# SOC_level_indicator.net
KiCad netlist of a schematic drawn in EAGLE
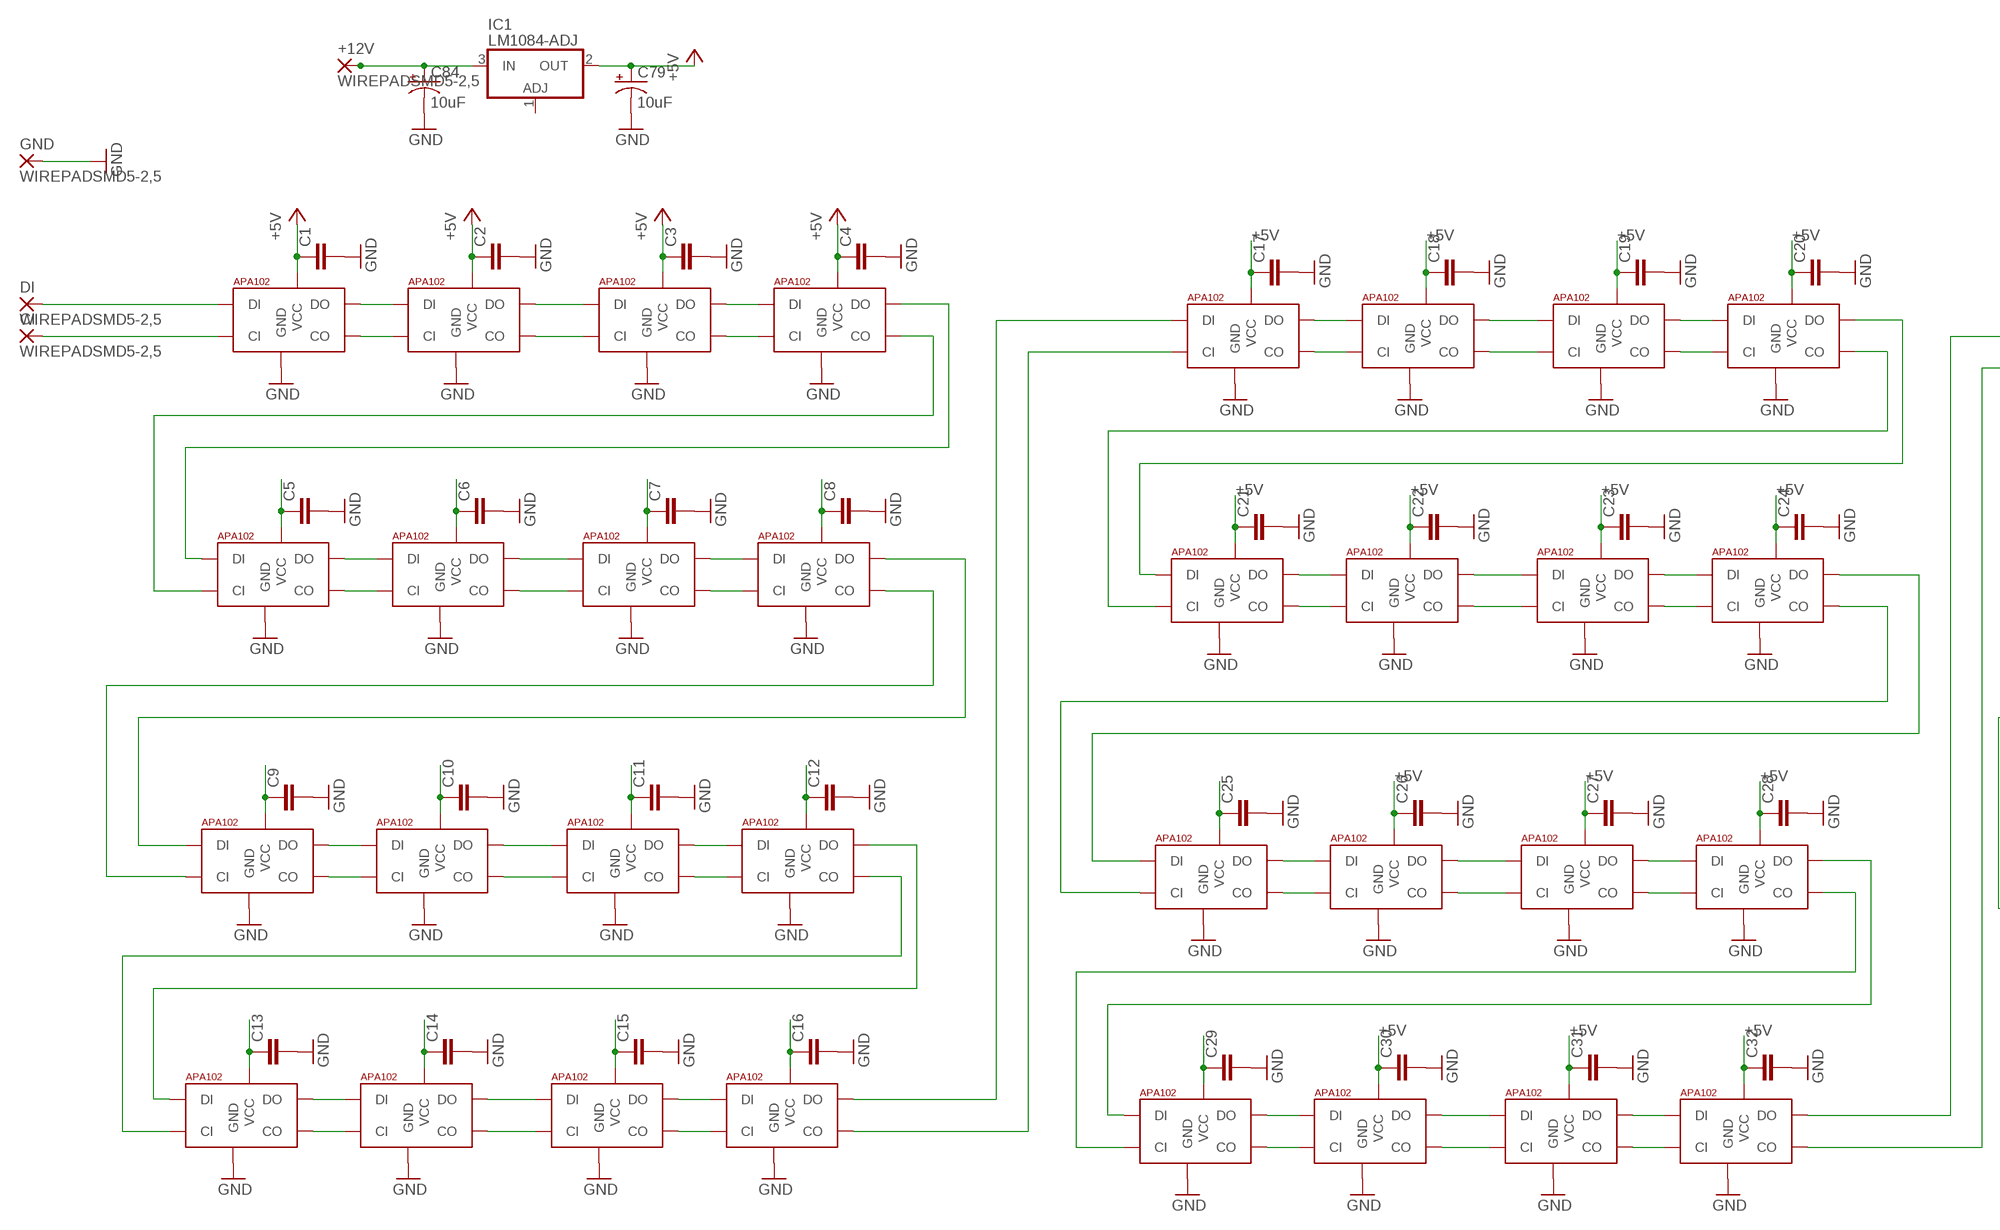
[diagram p0: schematic, sheet 1, part 1 of 2]
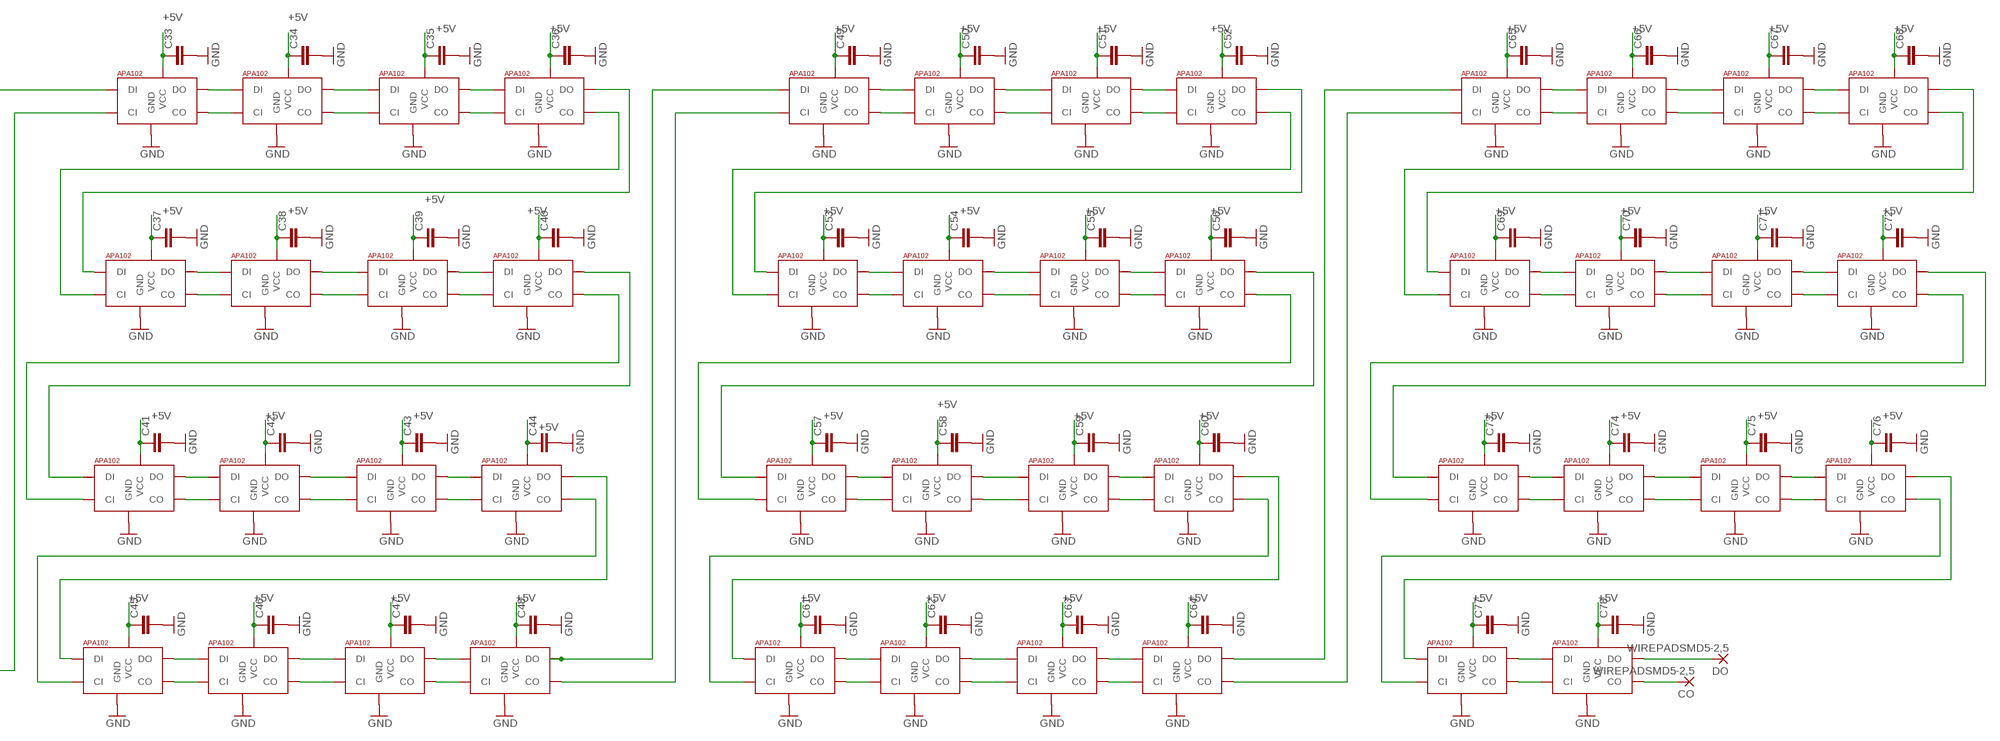
[diagram p1: schematic, sheet 1, part 2 of 2]

(export (version "E")
  (design (tool "Eeschema 10.0.6"))
  (components
    (comp (ref "+12V")
      (value "WIREPADSMD5-2,5")
      (footprint "eagle-import:5-2,5")
      (libsource (lib "eagle-import") (part "WIREPADSMD5-2,5"))
    )
    (comp (ref "C1")
      (value "CAP0603-CAP")
      (footprint "eagle-import:0603-CAP")
      (libsource (lib "eagle-import") (part "CAP0603-CAP"))
    )
    (comp (ref "C2")
      (value "CAP0603-CAP")
      (footprint "eagle-import:0603-CAP")
      (libsource (lib "eagle-import") (part "CAP0603-CAP"))
    )
    (comp (ref "C3")
      (value "CAP0603-CAP")
      (footprint "eagle-import:0603-CAP")
      (libsource (lib "eagle-import") (part "CAP0603-CAP"))
    )
    (comp (ref "C4")
      (value "CAP0603-CAP")
      (footprint "eagle-import:0603-CAP")
      (libsource (lib "eagle-import") (part "CAP0603-CAP"))
    )
    (comp (ref "C5")
      (value "CAP0603-CAP")
      (footprint "eagle-import:0603-CAP")
      (libsource (lib "eagle-import") (part "CAP0603-CAP"))
    )
    (comp (ref "C6")
      (value "CAP0603-CAP")
      (footprint "eagle-import:0603-CAP")
      (libsource (lib "eagle-import") (part "CAP0603-CAP"))
    )
    (comp (ref "C7")
      (value "CAP0603-CAP")
      (footprint "eagle-import:0603-CAP")
      (libsource (lib "eagle-import") (part "CAP0603-CAP"))
    )
    (comp (ref "C8")
      (value "CAP0603-CAP")
      (footprint "eagle-import:0603-CAP")
      (libsource (lib "eagle-import") (part "CAP0603-CAP"))
    )
    (comp (ref "C9")
      (value "CAP0603-CAP")
      (footprint "eagle-import:0603-CAP")
      (libsource (lib "eagle-import") (part "CAP0603-CAP"))
    )
    (comp (ref "C10")
      (value "CAP0603-CAP")
      (footprint "eagle-import:0603-CAP")
      (libsource (lib "eagle-import") (part "CAP0603-CAP"))
    )
    (comp (ref "C11")
      (value "CAP0603-CAP")
      (footprint "eagle-import:0603-CAP")
      (libsource (lib "eagle-import") (part "CAP0603-CAP"))
    )
    (comp (ref "C12")
      (value "CAP0603-CAP")
      (footprint "eagle-import:0603-CAP")
      (libsource (lib "eagle-import") (part "CAP0603-CAP"))
    )
    (comp (ref "C13")
      (value "CAP0603-CAP")
      (footprint "eagle-import:0603-CAP")
      (libsource (lib "eagle-import") (part "CAP0603-CAP"))
    )
    (comp (ref "C14")
      (value "CAP0603-CAP")
      (footprint "eagle-import:0603-CAP")
      (libsource (lib "eagle-import") (part "CAP0603-CAP"))
    )
    (comp (ref "C15")
      (value "CAP0603-CAP")
      (footprint "eagle-import:0603-CAP")
      (libsource (lib "eagle-import") (part "CAP0603-CAP"))
    )
    (comp (ref "C16")
      (value "CAP0603-CAP")
      (footprint "eagle-import:0603-CAP")
      (libsource (lib "eagle-import") (part "CAP0603-CAP"))
    )
    (comp (ref "C17")
      (value "CAP0603-CAP")
      (footprint "eagle-import:0603-CAP")
      (libsource (lib "eagle-import") (part "CAP0603-CAP"))
    )
    (comp (ref "C18")
      (value "CAP0603-CAP")
      (footprint "eagle-import:0603-CAP")
      (libsource (lib "eagle-import") (part "CAP0603-CAP"))
    )
    (comp (ref "C19")
      (value "CAP0603-CAP")
      (footprint "eagle-import:0603-CAP")
      (libsource (lib "eagle-import") (part "CAP0603-CAP"))
    )
    (comp (ref "C20")
      (value "CAP0603-CAP")
      (footprint "eagle-import:0603-CAP")
      (libsource (lib "eagle-import") (part "CAP0603-CAP"))
    )
    (comp (ref "C21")
      (value "CAP0603-CAP")
      (footprint "eagle-import:0603-CAP")
      (libsource (lib "eagle-import") (part "CAP0603-CAP"))
    )
    (comp (ref "C22")
      (value "CAP0603-CAP")
      (footprint "eagle-import:0603-CAP")
      (libsource (lib "eagle-import") (part "CAP0603-CAP"))
    )
    (comp (ref "C23")
      (value "CAP0603-CAP")
      (footprint "eagle-import:0603-CAP")
      (libsource (lib "eagle-import") (part "CAP0603-CAP"))
    )
    (comp (ref "C24")
      (value "CAP0603-CAP")
      (footprint "eagle-import:0603-CAP")
      (libsource (lib "eagle-import") (part "CAP0603-CAP"))
    )
    (comp (ref "C25")
      (value "CAP0603-CAP")
      (footprint "eagle-import:0603-CAP")
      (libsource (lib "eagle-import") (part "CAP0603-CAP"))
    )
    (comp (ref "C26")
      (value "CAP0603-CAP")
      (footprint "eagle-import:0603-CAP")
      (libsource (lib "eagle-import") (part "CAP0603-CAP"))
    )
    (comp (ref "C27")
      (value "CAP0603-CAP")
      (footprint "eagle-import:0603-CAP")
      (libsource (lib "eagle-import") (part "CAP0603-CAP"))
    )
    (comp (ref "C28")
      (value "CAP0603-CAP")
      (footprint "eagle-import:0603-CAP")
      (libsource (lib "eagle-import") (part "CAP0603-CAP"))
    )
    (comp (ref "C29")
      (value "CAP0603-CAP")
      (footprint "eagle-import:0603-CAP")
      (libsource (lib "eagle-import") (part "CAP0603-CAP"))
    )
    (comp (ref "C30")
      (value "CAP0603-CAP")
      (footprint "eagle-import:0603-CAP")
      (libsource (lib "eagle-import") (part "CAP0603-CAP"))
    )
    (comp (ref "C31")
      (value "CAP0603-CAP")
      (footprint "eagle-import:0603-CAP")
      (libsource (lib "eagle-import") (part "CAP0603-CAP"))
    )
    (comp (ref "C32")
      (value "CAP0603-CAP")
      (footprint "eagle-import:0603-CAP")
      (libsource (lib "eagle-import") (part "CAP0603-CAP"))
    )
    (comp (ref "C33")
      (value "CAP0603-CAP")
      (footprint "eagle-import:0603-CAP")
      (libsource (lib "eagle-import") (part "CAP0603-CAP"))
    )
    (comp (ref "C34")
      (value "CAP0603-CAP")
      (footprint "eagle-import:0603-CAP")
      (libsource (lib "eagle-import") (part "CAP0603-CAP"))
    )
    (comp (ref "C35")
      (value "CAP0603-CAP")
      (footprint "eagle-import:0603-CAP")
      (libsource (lib "eagle-import") (part "CAP0603-CAP"))
    )
    (comp (ref "C36")
      (value "CAP0603-CAP")
      (footprint "eagle-import:0603-CAP")
      (libsource (lib "eagle-import") (part "CAP0603-CAP"))
    )
    (comp (ref "C37")
      (value "CAP0603-CAP")
      (footprint "eagle-import:0603-CAP")
      (libsource (lib "eagle-import") (part "CAP0603-CAP"))
    )
    (comp (ref "C38")
      (value "CAP0603-CAP")
      (footprint "eagle-import:0603-CAP")
      (libsource (lib "eagle-import") (part "CAP0603-CAP"))
    )
    (comp (ref "C39")
      (value "CAP0603-CAP")
      (footprint "eagle-import:0603-CAP")
      (libsource (lib "eagle-import") (part "CAP0603-CAP"))
    )
    (comp (ref "C40")
      (value "CAP0603-CAP")
      (footprint "eagle-import:0603-CAP")
      (libsource (lib "eagle-import") (part "CAP0603-CAP"))
    )
    (comp (ref "C41")
      (value "CAP0603-CAP")
      (footprint "eagle-import:0603-CAP")
      (libsource (lib "eagle-import") (part "CAP0603-CAP"))
    )
    (comp (ref "C42")
      (value "CAP0603-CAP")
      (footprint "eagle-import:0603-CAP")
      (libsource (lib "eagle-import") (part "CAP0603-CAP"))
    )
    (comp (ref "C43")
      (value "CAP0603-CAP")
      (footprint "eagle-import:0603-CAP")
      (libsource (lib "eagle-import") (part "CAP0603-CAP"))
    )
    (comp (ref "C44")
      (value "CAP0603-CAP")
      (footprint "eagle-import:0603-CAP")
      (libsource (lib "eagle-import") (part "CAP0603-CAP"))
    )
    (comp (ref "C45")
      (value "CAP0603-CAP")
      (footprint "eagle-import:0603-CAP")
      (libsource (lib "eagle-import") (part "CAP0603-CAP"))
    )
    (comp (ref "C46")
      (value "CAP0603-CAP")
      (footprint "eagle-import:0603-CAP")
      (libsource (lib "eagle-import") (part "CAP0603-CAP"))
    )
    (comp (ref "C47")
      (value "CAP0603-CAP")
      (footprint "eagle-import:0603-CAP")
      (libsource (lib "eagle-import") (part "CAP0603-CAP"))
    )
    (comp (ref "C48")
      (value "CAP0603-CAP")
      (footprint "eagle-import:0603-CAP")
      (libsource (lib "eagle-import") (part "CAP0603-CAP"))
    )
    (comp (ref "C49")
      (value "CAP0603-CAP")
      (footprint "eagle-import:0603-CAP")
      (libsource (lib "eagle-import") (part "CAP0603-CAP"))
    )
    (comp (ref "C50")
      (value "CAP0603-CAP")
      (footprint "eagle-import:0603-CAP")
      (libsource (lib "eagle-import") (part "CAP0603-CAP"))
    )
    (comp (ref "C51")
      (value "CAP0603-CAP")
      (footprint "eagle-import:0603-CAP")
      (libsource (lib "eagle-import") (part "CAP0603-CAP"))
    )
    (comp (ref "C52")
      (value "CAP0603-CAP")
      (footprint "eagle-import:0603-CAP")
      (libsource (lib "eagle-import") (part "CAP0603-CAP"))
    )
    (comp (ref "C53")
      (value "CAP0603-CAP")
      (footprint "eagle-import:0603-CAP")
      (libsource (lib "eagle-import") (part "CAP0603-CAP"))
    )
    (comp (ref "C54")
      (value "CAP0603-CAP")
      (footprint "eagle-import:0603-CAP")
      (libsource (lib "eagle-import") (part "CAP0603-CAP"))
    )
    (comp (ref "C55")
      (value "CAP0603-CAP")
      (footprint "eagle-import:0603-CAP")
      (libsource (lib "eagle-import") (part "CAP0603-CAP"))
    )
    (comp (ref "C56")
      (value "CAP0603-CAP")
      (footprint "eagle-import:0603-CAP")
      (libsource (lib "eagle-import") (part "CAP0603-CAP"))
    )
    (comp (ref "C57")
      (value "CAP0603-CAP")
      (footprint "eagle-import:0603-CAP")
      (libsource (lib "eagle-import") (part "CAP0603-CAP"))
    )
    (comp (ref "C58")
      (value "CAP0603-CAP")
      (footprint "eagle-import:0603-CAP")
      (libsource (lib "eagle-import") (part "CAP0603-CAP"))
    )
    (comp (ref "C59")
      (value "CAP0603-CAP")
      (footprint "eagle-import:0603-CAP")
      (libsource (lib "eagle-import") (part "CAP0603-CAP"))
    )
    (comp (ref "C60")
      (value "CAP0603-CAP")
      (footprint "eagle-import:0603-CAP")
      (libsource (lib "eagle-import") (part "CAP0603-CAP"))
    )
    (comp (ref "C61")
      (value "CAP0603-CAP")
      (footprint "eagle-import:0603-CAP")
      (libsource (lib "eagle-import") (part "CAP0603-CAP"))
    )
    (comp (ref "C62")
      (value "CAP0603-CAP")
      (footprint "eagle-import:0603-CAP")
      (libsource (lib "eagle-import") (part "CAP0603-CAP"))
    )
    (comp (ref "C63")
      (value "CAP0603-CAP")
      (footprint "eagle-import:0603-CAP")
      (libsource (lib "eagle-import") (part "CAP0603-CAP"))
    )
    (comp (ref "C64")
      (value "CAP0603-CAP")
      (footprint "eagle-import:0603-CAP")
      (libsource (lib "eagle-import") (part "CAP0603-CAP"))
    )
    (comp (ref "C65")
      (value "CAP0603-CAP")
      (footprint "eagle-import:0603-CAP")
      (libsource (lib "eagle-import") (part "CAP0603-CAP"))
    )
    (comp (ref "C66")
      (value "CAP0603-CAP")
      (footprint "eagle-import:0603-CAP")
      (libsource (lib "eagle-import") (part "CAP0603-CAP"))
    )
    (comp (ref "C67")
      (value "CAP0603-CAP")
      (footprint "eagle-import:0603-CAP")
      (libsource (lib "eagle-import") (part "CAP0603-CAP"))
    )
    (comp (ref "C68")
      (value "CAP0603-CAP")
      (footprint "eagle-import:0603-CAP")
      (libsource (lib "eagle-import") (part "CAP0603-CAP"))
    )
    (comp (ref "C69")
      (value "CAP0603-CAP")
      (footprint "eagle-import:0603-CAP")
      (libsource (lib "eagle-import") (part "CAP0603-CAP"))
    )
    (comp (ref "C70")
      (value "CAP0603-CAP")
      (footprint "eagle-import:0603-CAP")
      (libsource (lib "eagle-import") (part "CAP0603-CAP"))
    )
    (comp (ref "C71")
      (value "CAP0603-CAP")
      (footprint "eagle-import:0603-CAP")
      (libsource (lib "eagle-import") (part "CAP0603-CAP"))
    )
    (comp (ref "C72")
      (value "CAP0603-CAP")
      (footprint "eagle-import:0603-CAP")
      (libsource (lib "eagle-import") (part "CAP0603-CAP"))
    )
    (comp (ref "C73")
      (value "CAP0603-CAP")
      (footprint "eagle-import:0603-CAP")
      (libsource (lib "eagle-import") (part "CAP0603-CAP"))
    )
    (comp (ref "C74")
      (value "CAP0603-CAP")
      (footprint "eagle-import:0603-CAP")
      (libsource (lib "eagle-import") (part "CAP0603-CAP"))
    )
    (comp (ref "C75")
      (value "CAP0603-CAP")
      (footprint "eagle-import:0603-CAP")
      (libsource (lib "eagle-import") (part "CAP0603-CAP"))
    )
    (comp (ref "C76")
      (value "CAP0603-CAP")
      (footprint "eagle-import:0603-CAP")
      (libsource (lib "eagle-import") (part "CAP0603-CAP"))
    )
    (comp (ref "C77")
      (value "CAP0603-CAP")
      (footprint "eagle-import:0603-CAP")
      (libsource (lib "eagle-import") (part "CAP0603-CAP"))
    )
    (comp (ref "C78")
      (value "CAP0603-CAP")
      (footprint "eagle-import:0603-CAP")
      (libsource (lib "eagle-import") (part "CAP0603-CAP"))
    )
    (comp (ref "C79")
      (value "10uF")
      (footprint "eagle-import:EIA3216")
      (libsource (lib "eagle-import") (part "10UF-16V-10%(TANT)"))
    )
    (comp (ref "C84")
      (value "10uF")
      (footprint "eagle-import:EIA3216")
      (libsource (lib "eagle-import") (part "10UF-16V-10%(TANT)"))
    )
    (comp (ref "CI")
      (value "WIREPADSMD5-2,5")
      (footprint "eagle-import:5-2,5")
      (libsource (lib "eagle-import") (part "WIREPADSMD5-2,5"))
    )
    (comp (ref "CO")
      (value "WIREPADSMD5-2,5")
      (footprint "eagle-import:5-2,5")
      (libsource (lib "eagle-import") (part "WIREPADSMD5-2,5"))
    )
    (comp (ref "DI")
      (value "WIREPADSMD5-2,5")
      (footprint "eagle-import:5-2,5")
      (libsource (lib "eagle-import") (part "WIREPADSMD5-2,5"))
    )
    (comp (ref "DO")
      (value "WIREPADSMD5-2,5")
      (footprint "eagle-import:5-2,5")
      (libsource (lib "eagle-import") (part "WIREPADSMD5-2,5"))
    )
    (comp (ref "GND")
      (value "WIREPADSMD5-2,5")
      (footprint "eagle-import:5-2,5")
      (libsource (lib "eagle-import") (part "WIREPADSMD5-2,5"))
    )
    (comp (ref "IC1")
      (value "LM1084-ADJ")
      (footprint "eagle-import:TO263-3")
      (libsource (lib "eagle-import") (part "LM1084-ADJ"))
    )
    (comp (ref "U$1")
      (value "APA1025050")
      (footprint "eagle-import:APA102_5050")
      (libsource (lib "eagle-import") (part "APA1025050"))
    )
    (comp (ref "U$2")
      (value "APA1025050")
      (footprint "eagle-import:APA102_5050")
      (libsource (lib "eagle-import") (part "APA1025050"))
    )
    (comp (ref "U$3")
      (value "APA1025050")
      (footprint "eagle-import:APA102_5050")
      (libsource (lib "eagle-import") (part "APA1025050"))
    )
    (comp (ref "U$4")
      (value "APA1025050")
      (footprint "eagle-import:APA102_5050")
      (libsource (lib "eagle-import") (part "APA1025050"))
    )
    (comp (ref "U$5")
      (value "APA1025050")
      (footprint "eagle-import:APA102_5050")
      (libsource (lib "eagle-import") (part "APA1025050"))
    )
    (comp (ref "U$6")
      (value "APA1025050")
      (footprint "eagle-import:APA102_5050")
      (libsource (lib "eagle-import") (part "APA1025050"))
    )
    (comp (ref "U$7")
      (value "APA1025050")
      (footprint "eagle-import:APA102_5050")
      (libsource (lib "eagle-import") (part "APA1025050"))
    )
    (comp (ref "U$8")
      (value "APA1025050")
      (footprint "eagle-import:APA102_5050")
      (libsource (lib "eagle-import") (part "APA1025050"))
    )
    (comp (ref "U$9")
      (value "APA1025050")
      (footprint "eagle-import:APA102_5050")
      (libsource (lib "eagle-import") (part "APA1025050"))
    )
    (comp (ref "U$10")
      (value "APA1025050")
      (footprint "eagle-import:APA102_5050")
      (libsource (lib "eagle-import") (part "APA1025050"))
    )
    (comp (ref "U$11")
      (value "APA1025050")
      (footprint "eagle-import:APA102_5050")
      (libsource (lib "eagle-import") (part "APA1025050"))
    )
    (comp (ref "U$12")
      (value "APA1025050")
      (footprint "eagle-import:APA102_5050")
      (libsource (lib "eagle-import") (part "APA1025050"))
    )
    (comp (ref "U$13")
      (value "APA1025050")
      (footprint "eagle-import:APA102_5050")
      (libsource (lib "eagle-import") (part "APA1025050"))
    )
    (comp (ref "U$14")
      (value "APA1025050")
      (footprint "eagle-import:APA102_5050")
      (libsource (lib "eagle-import") (part "APA1025050"))
    )
    (comp (ref "U$15")
      (value "APA1025050")
      (footprint "eagle-import:APA102_5050")
      (libsource (lib "eagle-import") (part "APA1025050"))
    )
    (comp (ref "U$16")
      (value "APA1025050")
      (footprint "eagle-import:APA102_5050")
      (libsource (lib "eagle-import") (part "APA1025050"))
    )
    (comp (ref "U$17")
      (value "APA1025050")
      (footprint "eagle-import:APA102_5050")
      (libsource (lib "eagle-import") (part "APA1025050"))
    )
    (comp (ref "U$18")
      (value "APA1025050")
      (footprint "eagle-import:APA102_5050")
      (libsource (lib "eagle-import") (part "APA1025050"))
    )
    (comp (ref "U$19")
      (value "APA1025050")
      (footprint "eagle-import:APA102_5050")
      (libsource (lib "eagle-import") (part "APA1025050"))
    )
    (comp (ref "U$20")
      (value "APA1025050")
      (footprint "eagle-import:APA102_5050")
      (libsource (lib "eagle-import") (part "APA1025050"))
    )
    (comp (ref "U$21")
      (value "APA1025050")
      (footprint "eagle-import:APA102_5050")
      (libsource (lib "eagle-import") (part "APA1025050"))
    )
    (comp (ref "U$22")
      (value "APA1025050")
      (footprint "eagle-import:APA102_5050")
      (libsource (lib "eagle-import") (part "APA1025050"))
    )
    (comp (ref "U$23")
      (value "APA1025050")
      (footprint "eagle-import:APA102_5050")
      (libsource (lib "eagle-import") (part "APA1025050"))
    )
    (comp (ref "U$24")
      (value "APA1025050")
      (footprint "eagle-import:APA102_5050")
      (libsource (lib "eagle-import") (part "APA1025050"))
    )
    (comp (ref "U$25")
      (value "APA1025050")
      (footprint "eagle-import:APA102_5050")
      (libsource (lib "eagle-import") (part "APA1025050"))
    )
    (comp (ref "U$26")
      (value "APA1025050")
      (footprint "eagle-import:APA102_5050")
      (libsource (lib "eagle-import") (part "APA1025050"))
    )
    (comp (ref "U$27")
      (value "APA1025050")
      (footprint "eagle-import:APA102_5050")
      (libsource (lib "eagle-import") (part "APA1025050"))
    )
    (comp (ref "U$28")
      (value "APA1025050")
      (footprint "eagle-import:APA102_5050")
      (libsource (lib "eagle-import") (part "APA1025050"))
    )
    (comp (ref "U$29")
      (value "APA1025050")
      (footprint "eagle-import:APA102_5050")
      (libsource (lib "eagle-import") (part "APA1025050"))
    )
    (comp (ref "U$30")
      (value "APA1025050")
      (footprint "eagle-import:APA102_5050")
      (libsource (lib "eagle-import") (part "APA1025050"))
    )
    (comp (ref "U$31")
      (value "APA1025050")
      (footprint "eagle-import:APA102_5050")
      (libsource (lib "eagle-import") (part "APA1025050"))
    )
    (comp (ref "U$32")
      (value "APA1025050")
      (footprint "eagle-import:APA102_5050")
      (libsource (lib "eagle-import") (part "APA1025050"))
    )
    (comp (ref "U$33")
      (value "APA1025050")
      (footprint "eagle-import:APA102_5050")
      (libsource (lib "eagle-import") (part "APA1025050"))
    )
    (comp (ref "U$34")
      (value "APA1025050")
      (footprint "eagle-import:APA102_5050")
      (libsource (lib "eagle-import") (part "APA1025050"))
    )
    (comp (ref "U$35")
      (value "APA1025050")
      (footprint "eagle-import:APA102_5050")
      (libsource (lib "eagle-import") (part "APA1025050"))
    )
    (comp (ref "U$36")
      (value "APA1025050")
      (footprint "eagle-import:APA102_5050")
      (libsource (lib "eagle-import") (part "APA1025050"))
    )
    (comp (ref "U$37")
      (value "APA1025050")
      (footprint "eagle-import:APA102_5050")
      (libsource (lib "eagle-import") (part "APA1025050"))
    )
    (comp (ref "U$38")
      (value "APA1025050")
      (footprint "eagle-import:APA102_5050")
      (libsource (lib "eagle-import") (part "APA1025050"))
    )
    (comp (ref "U$39")
      (value "APA1025050")
      (footprint "eagle-import:APA102_5050")
      (libsource (lib "eagle-import") (part "APA1025050"))
    )
    (comp (ref "U$40")
      (value "APA1025050")
      (footprint "eagle-import:APA102_5050")
      (libsource (lib "eagle-import") (part "APA1025050"))
    )
    (comp (ref "U$41")
      (value "APA1025050")
      (footprint "eagle-import:APA102_5050")
      (libsource (lib "eagle-import") (part "APA1025050"))
    )
    (comp (ref "U$42")
      (value "APA1025050")
      (footprint "eagle-import:APA102_5050")
      (libsource (lib "eagle-import") (part "APA1025050"))
    )
    (comp (ref "U$43")
      (value "APA1025050")
      (footprint "eagle-import:APA102_5050")
      (libsource (lib "eagle-import") (part "APA1025050"))
    )
    (comp (ref "U$44")
      (value "APA1025050")
      (footprint "eagle-import:APA102_5050")
      (libsource (lib "eagle-import") (part "APA1025050"))
    )
    (comp (ref "U$45")
      (value "APA1025050")
      (footprint "eagle-import:APA102_5050")
      (libsource (lib "eagle-import") (part "APA1025050"))
    )
    (comp (ref "U$46")
      (value "APA1025050")
      (footprint "eagle-import:APA102_5050")
      (libsource (lib "eagle-import") (part "APA1025050"))
    )
    (comp (ref "U$47")
      (value "APA1025050")
      (footprint "eagle-import:APA102_5050")
      (libsource (lib "eagle-import") (part "APA1025050"))
    )
    (comp (ref "U$48")
      (value "APA1025050")
      (footprint "eagle-import:APA102_5050")
      (libsource (lib "eagle-import") (part "APA1025050"))
    )
    (comp (ref "U$49")
      (value "APA1025050")
      (footprint "eagle-import:APA102_5050")
      (libsource (lib "eagle-import") (part "APA1025050"))
    )
    (comp (ref "U$50")
      (value "APA1025050")
      (footprint "eagle-import:APA102_5050")
      (libsource (lib "eagle-import") (part "APA1025050"))
    )
    (comp (ref "U$51")
      (value "APA1025050")
      (footprint "eagle-import:APA102_5050")
      (libsource (lib "eagle-import") (part "APA1025050"))
    )
    (comp (ref "U$52")
      (value "APA1025050")
      (footprint "eagle-import:APA102_5050")
      (libsource (lib "eagle-import") (part "APA1025050"))
    )
    (comp (ref "U$53")
      (value "APA1025050")
      (footprint "eagle-import:APA102_5050")
      (libsource (lib "eagle-import") (part "APA1025050"))
    )
    (comp (ref "U$54")
      (value "APA1025050")
      (footprint "eagle-import:APA102_5050")
      (libsource (lib "eagle-import") (part "APA1025050"))
    )
    (comp (ref "U$55")
      (value "APA1025050")
      (footprint "eagle-import:APA102_5050")
      (libsource (lib "eagle-import") (part "APA1025050"))
    )
    (comp (ref "U$56")
      (value "APA1025050")
      (footprint "eagle-import:APA102_5050")
      (libsource (lib "eagle-import") (part "APA1025050"))
    )
    (comp (ref "U$57")
      (value "APA1025050")
      (footprint "eagle-import:APA102_5050")
      (libsource (lib "eagle-import") (part "APA1025050"))
    )
    (comp (ref "U$58")
      (value "APA1025050")
      (footprint "eagle-import:APA102_5050")
      (libsource (lib "eagle-import") (part "APA1025050"))
    )
    (comp (ref "U$59")
      (value "APA1025050")
      (footprint "eagle-import:APA102_5050")
      (libsource (lib "eagle-import") (part "APA1025050"))
    )
    (comp (ref "U$60")
      (value "APA1025050")
      (footprint "eagle-import:APA102_5050")
      (libsource (lib "eagle-import") (part "APA1025050"))
    )
    (comp (ref "U$61")
      (value "APA1025050")
      (footprint "eagle-import:APA102_5050")
      (libsource (lib "eagle-import") (part "APA1025050"))
    )
    (comp (ref "U$62")
      (value "APA1025050")
      (footprint "eagle-import:APA102_5050")
      (libsource (lib "eagle-import") (part "APA1025050"))
    )
    (comp (ref "U$63")
      (value "APA1025050")
      (footprint "eagle-import:APA102_5050")
      (libsource (lib "eagle-import") (part "APA1025050"))
    )
    (comp (ref "U$64")
      (value "APA1025050")
      (footprint "eagle-import:APA102_5050")
      (libsource (lib "eagle-import") (part "APA1025050"))
    )
    (comp (ref "U$65")
      (value "APA1025050")
      (footprint "eagle-import:APA102_5050")
      (libsource (lib "eagle-import") (part "APA1025050"))
    )
    (comp (ref "U$66")
      (value "APA1025050")
      (footprint "eagle-import:APA102_5050")
      (libsource (lib "eagle-import") (part "APA1025050"))
    )
    (comp (ref "U$67")
      (value "APA1025050")
      (footprint "eagle-import:APA102_5050")
      (libsource (lib "eagle-import") (part "APA1025050"))
    )
    (comp (ref "U$68")
      (value "APA1025050")
      (footprint "eagle-import:APA102_5050")
      (libsource (lib "eagle-import") (part "APA1025050"))
    )
    (comp (ref "U$69")
      (value "APA1025050")
      (footprint "eagle-import:APA102_5050")
      (libsource (lib "eagle-import") (part "APA1025050"))
    )
    (comp (ref "U$70")
      (value "APA1025050")
      (footprint "eagle-import:APA102_5050")
      (libsource (lib "eagle-import") (part "APA1025050"))
    )
    (comp (ref "U$71")
      (value "APA1025050")
      (footprint "eagle-import:APA102_5050")
      (libsource (lib "eagle-import") (part "APA1025050"))
    )
    (comp (ref "U$72")
      (value "APA1025050")
      (footprint "eagle-import:APA102_5050")
      (libsource (lib "eagle-import") (part "APA1025050"))
    )
    (comp (ref "U$73")
      (value "APA1025050")
      (footprint "eagle-import:APA102_5050")
      (libsource (lib "eagle-import") (part "APA1025050"))
    )
    (comp (ref "U$74")
      (value "APA1025050")
      (footprint "eagle-import:APA102_5050")
      (libsource (lib "eagle-import") (part "APA1025050"))
    )
    (comp (ref "U$75")
      (value "APA1025050")
      (footprint "eagle-import:APA102_5050")
      (libsource (lib "eagle-import") (part "APA1025050"))
    )
    (comp (ref "U$76")
      (value "APA1025050")
      (footprint "eagle-import:APA102_5050")
      (libsource (lib "eagle-import") (part "APA1025050"))
    )
    (comp (ref "U$77")
      (value "APA1025050")
      (footprint "eagle-import:APA102_5050")
      (libsource (lib "eagle-import") (part "APA1025050"))
    )
    (comp (ref "U$78")
      (value "APA1025050")
      (footprint "eagle-import:APA102_5050")
      (libsource (lib "eagle-import") (part "APA1025050"))
    )
  )
  (nets
    (net (code "1") (name "+5V") (class "Default")
      (node (ref "C1") (pin "1") (pinfunction "1_1") (pintype "passive"))
      (node (ref "C10") (pin "1") (pinfunction "1_1") (pintype "passive"))
      (node (ref "C11") (pin "1") (pinfunction "1_1") (pintype "passive"))
      (node (ref "C12") (pin "1") (pinfunction "1_1") (pintype "passive"))
      (node (ref "C13") (pin "1") (pinfunction "1_1") (pintype "passive"))
      (node (ref "C14") (pin "1") (pinfunction "1_1") (pintype "passive"))
      (node (ref "C15") (pin "1") (pinfunction "1_1") (pintype "passive"))
      (node (ref "C16") (pin "1") (pinfunction "1_1") (pintype "passive"))
      (node (ref "C17") (pin "1") (pinfunction "1_1") (pintype "passive"))
      (node (ref "C18") (pin "1") (pinfunction "1_1") (pintype "passive"))
      (node (ref "C19") (pin "1") (pinfunction "1_1") (pintype "passive"))
      (node (ref "C2") (pin "1") (pinfunction "1_1") (pintype "passive"))
      (node (ref "C20") (pin "1") (pinfunction "1_1") (pintype "passive"))
      (node (ref "C21") (pin "1") (pinfunction "1_1") (pintype "passive"))
      (node (ref "C22") (pin "1") (pinfunction "1_1") (pintype "passive"))
      (node (ref "C23") (pin "1") (pinfunction "1_1") (pintype "passive"))
      (node (ref "C24") (pin "1") (pinfunction "1_1") (pintype "passive"))
      (node (ref "C25") (pin "1") (pinfunction "1_1") (pintype "passive"))
      (node (ref "C26") (pin "1") (pinfunction "1_1") (pintype "passive"))
      (node (ref "C27") (pin "1") (pinfunction "1_1") (pintype "passive"))
      (node (ref "C28") (pin "1") (pinfunction "1_1") (pintype "passive"))
      (node (ref "C29") (pin "1") (pinfunction "1_1") (pintype "passive"))
      (node (ref "C3") (pin "1") (pinfunction "1_1") (pintype "passive"))
      (node (ref "C30") (pin "1") (pinfunction "1_1") (pintype "passive"))
      (node (ref "C31") (pin "1") (pinfunction "1_1") (pintype "passive"))
      (node (ref "C32") (pin "1") (pinfunction "1_1") (pintype "passive"))
      (node (ref "C33") (pin "1") (pinfunction "1_1") (pintype "passive"))
      (node (ref "C34") (pin "1") (pinfunction "1_1") (pintype "passive"))
      (node (ref "C35") (pin "1") (pinfunction "1_1") (pintype "passive"))
      (node (ref "C36") (pin "1") (pinfunction "1_1") (pintype "passive"))
      (node (ref "C37") (pin "1") (pinfunction "1_1") (pintype "passive"))
      (node (ref "C38") (pin "1") (pinfunction "1_1") (pintype "passive"))
      (node (ref "C39") (pin "1") (pinfunction "1_1") (pintype "passive"))
      (node (ref "C4") (pin "1") (pinfunction "1_1") (pintype "passive"))
      (node (ref "C40") (pin "1") (pinfunction "1_1") (pintype "passive"))
      (node (ref "C41") (pin "1") (pinfunction "1_1") (pintype "passive"))
      (node (ref "C42") (pin "1") (pinfunction "1_1") (pintype "passive"))
      (node (ref "C43") (pin "1") (pinfunction "1_1") (pintype "passive"))
      (node (ref "C44") (pin "1") (pinfunction "1_1") (pintype "passive"))
      (node (ref "C45") (pin "1") (pinfunction "1_1") (pintype "passive"))
      (node (ref "C46") (pin "1") (pinfunction "1_1") (pintype "passive"))
      (node (ref "C47") (pin "1") (pinfunction "1_1") (pintype "passive"))
      (node (ref "C48") (pin "1") (pinfunction "1_1") (pintype "passive"))
      (node (ref "C49") (pin "1") (pinfunction "1_1") (pintype "passive"))
      (node (ref "C5") (pin "1") (pinfunction "1_1") (pintype "passive"))
      (node (ref "C50") (pin "1") (pinfunction "1_1") (pintype "passive"))
      (node (ref "C51") (pin "1") (pinfunction "1_1") (pintype "passive"))
      (node (ref "C52") (pin "1") (pinfunction "1_1") (pintype "passive"))
      (node (ref "C53") (pin "1") (pinfunction "1_1") (pintype "passive"))
      (node (ref "C54") (pin "1") (pinfunction "1_1") (pintype "passive"))
      (node (ref "C55") (pin "1") (pinfunction "1_1") (pintype "passive"))
      (node (ref "C56") (pin "1") (pinfunction "1_1") (pintype "passive"))
      (node (ref "C57") (pin "1") (pinfunction "1_1") (pintype "passive"))
      (node (ref "C58") (pin "1") (pinfunction "1_1") (pintype "passive"))
      (node (ref "C59") (pin "1") (pinfunction "1_1") (pintype "passive"))
      (node (ref "C6") (pin "1") (pinfunction "1_1") (pintype "passive"))
      (node (ref "C60") (pin "1") (pinfunction "1_1") (pintype "passive"))
      (node (ref "C61") (pin "1") (pinfunction "1_1") (pintype "passive"))
      (node (ref "C62") (pin "1") (pinfunction "1_1") (pintype "passive"))
      (node (ref "C63") (pin "1") (pinfunction "1_1") (pintype "passive"))
      (node (ref "C64") (pin "1") (pinfunction "1_1") (pintype "passive"))
      (node (ref "C65") (pin "1") (pinfunction "1_1") (pintype "passive"))
      (node (ref "C66") (pin "1") (pinfunction "1_1") (pintype "passive"))
      (node (ref "C67") (pin "1") (pinfunction "1_1") (pintype "passive"))
      (node (ref "C68") (pin "1") (pinfunction "1_1") (pintype "passive"))
      (node (ref "C69") (pin "1") (pinfunction "1_1") (pintype "passive"))
      (node (ref "C7") (pin "1") (pinfunction "1_1") (pintype "passive"))
      (node (ref "C70") (pin "1") (pinfunction "1_1") (pintype "passive"))
      (node (ref "C71") (pin "1") (pinfunction "1_1") (pintype "passive"))
      (node (ref "C72") (pin "1") (pinfunction "1_1") (pintype "passive"))
      (node (ref "C73") (pin "1") (pinfunction "1_1") (pintype "passive"))
      (node (ref "C74") (pin "1") (pinfunction "1_1") (pintype "passive"))
      (node (ref "C75") (pin "1") (pinfunction "1_1") (pintype "passive"))
      (node (ref "C76") (pin "1") (pinfunction "1_1") (pintype "passive"))
      (node (ref "C77") (pin "1") (pinfunction "1_1") (pintype "passive"))
      (node (ref "C78") (pin "1") (pinfunction "1_1") (pintype "passive"))
      (node (ref "C79") (pin "A") (pinfunction "+_A") (pintype "passive"))
      (node (ref "C8") (pin "1") (pinfunction "1_1") (pintype "passive"))
      (node (ref "C9") (pin "1") (pinfunction "1_1") (pintype "passive"))
      (node (ref "IC1") (pin "2") (pinfunction "OUT_2") (pintype "output"))
      (node (ref "U$1") (pin "1") (pinfunction "VCC_1") (pintype "bidirectional"))
      (node (ref "U$10") (pin "1") (pinfunction "VCC_1") (pintype "bidirectional"))
      (node (ref "U$11") (pin "1") (pinfunction "VCC_1") (pintype "bidirectional"))
      (node (ref "U$12") (pin "1") (pinfunction "VCC_1") (pintype "bidirectional"))
      (node (ref "U$13") (pin "1") (pinfunction "VCC_1") (pintype "bidirectional"))
      (node (ref "U$14") (pin "1") (pinfunction "VCC_1") (pintype "bidirectional"))
      (node (ref "U$15") (pin "1") (pinfunction "VCC_1") (pintype "bidirectional"))
      (node (ref "U$16") (pin "1") (pinfunction "VCC_1") (pintype "bidirectional"))
      (node (ref "U$17") (pin "1") (pinfunction "VCC_1") (pintype "bidirectional"))
      (node (ref "U$18") (pin "1") (pinfunction "VCC_1") (pintype "bidirectional"))
      (node (ref "U$19") (pin "1") (pinfunction "VCC_1") (pintype "bidirectional"))
      (node (ref "U$2") (pin "1") (pinfunction "VCC_1") (pintype "bidirectional"))
      (node (ref "U$20") (pin "1") (pinfunction "VCC_1") (pintype "bidirectional"))
      (node (ref "U$21") (pin "1") (pinfunction "VCC_1") (pintype "bidirectional"))
      (node (ref "U$22") (pin "1") (pinfunction "VCC_1") (pintype "bidirectional"))
      (node (ref "U$23") (pin "1") (pinfunction "VCC_1") (pintype "bidirectional"))
      (node (ref "U$24") (pin "1") (pinfunction "VCC_1") (pintype "bidirectional"))
      (node (ref "U$25") (pin "1") (pinfunction "VCC_1") (pintype "bidirectional"))
      (node (ref "U$26") (pin "1") (pinfunction "VCC_1") (pintype "bidirectional"))
      (node (ref "U$27") (pin "1") (pinfunction "VCC_1") (pintype "bidirectional"))
      (node (ref "U$28") (pin "1") (pinfunction "VCC_1") (pintype "bidirectional"))
      (node (ref "U$29") (pin "1") (pinfunction "VCC_1") (pintype "bidirectional"))
      (node (ref "U$3") (pin "1") (pinfunction "VCC_1") (pintype "bidirectional"))
      (node (ref "U$30") (pin "1") (pinfunction "VCC_1") (pintype "bidirectional"))
      (node (ref "U$31") (pin "1") (pinfunction "VCC_1") (pintype "bidirectional"))
      (node (ref "U$32") (pin "1") (pinfunction "VCC_1") (pintype "bidirectional"))
      (node (ref "U$33") (pin "1") (pinfunction "VCC_1") (pintype "bidirectional"))
      (node (ref "U$34") (pin "1") (pinfunction "VCC_1") (pintype "bidirectional"))
      (node (ref "U$35") (pin "1") (pinfunction "VCC_1") (pintype "bidirectional"))
      (node (ref "U$36") (pin "1") (pinfunction "VCC_1") (pintype "bidirectional"))
      (node (ref "U$37") (pin "1") (pinfunction "VCC_1") (pintype "bidirectional"))
      (node (ref "U$38") (pin "1") (pinfunction "VCC_1") (pintype "bidirectional"))
      (node (ref "U$39") (pin "1") (pinfunction "VCC_1") (pintype "bidirectional"))
      (node (ref "U$4") (pin "1") (pinfunction "VCC_1") (pintype "bidirectional"))
      (node (ref "U$40") (pin "1") (pinfunction "VCC_1") (pintype "bidirectional"))
      (node (ref "U$41") (pin "1") (pinfunction "VCC_1") (pintype "bidirectional"))
      (node (ref "U$42") (pin "1") (pinfunction "VCC_1") (pintype "bidirectional"))
      (node (ref "U$43") (pin "1") (pinfunction "VCC_1") (pintype "bidirectional"))
      (node (ref "U$44") (pin "1") (pinfunction "VCC_1") (pintype "bidirectional"))
      (node (ref "U$45") (pin "1") (pinfunction "VCC_1") (pintype "bidirectional"))
      (node (ref "U$46") (pin "1") (pinfunction "VCC_1") (pintype "bidirectional"))
      (node (ref "U$47") (pin "1") (pinfunction "VCC_1") (pintype "bidirectional"))
      (node (ref "U$48") (pin "1") (pinfunction "VCC_1") (pintype "bidirectional"))
      (node (ref "U$49") (pin "1") (pinfunction "VCC_1") (pintype "bidirectional"))
      (node (ref "U$5") (pin "1") (pinfunction "VCC_1") (pintype "bidirectional"))
      (node (ref "U$50") (pin "1") (pinfunction "VCC_1") (pintype "bidirectional"))
      (node (ref "U$51") (pin "1") (pinfunction "VCC_1") (pintype "bidirectional"))
      (node (ref "U$52") (pin "1") (pinfunction "VCC_1") (pintype "bidirectional"))
      (node (ref "U$53") (pin "1") (pinfunction "VCC_1") (pintype "bidirectional"))
      (node (ref "U$54") (pin "1") (pinfunction "VCC_1") (pintype "bidirectional"))
      (node (ref "U$55") (pin "1") (pinfunction "VCC_1") (pintype "bidirectional"))
      (node (ref "U$56") (pin "1") (pinfunction "VCC_1") (pintype "bidirectional"))
      (node (ref "U$57") (pin "1") (pinfunction "VCC_1") (pintype "bidirectional"))
      (node (ref "U$58") (pin "1") (pinfunction "VCC_1") (pintype "bidirectional"))
      (node (ref "U$59") (pin "1") (pinfunction "VCC_1") (pintype "bidirectional"))
      (node (ref "U$6") (pin "1") (pinfunction "VCC_1") (pintype "bidirectional"))
      (node (ref "U$60") (pin "1") (pinfunction "VCC_1") (pintype "bidirectional"))
      (node (ref "U$61") (pin "1") (pinfunction "VCC_1") (pintype "bidirectional"))
      (node (ref "U$62") (pin "1") (pinfunction "VCC_1") (pintype "bidirectional"))
      (node (ref "U$63") (pin "1") (pinfunction "VCC_1") (pintype "bidirectional"))
      (node (ref "U$64") (pin "1") (pinfunction "VCC_1") (pintype "bidirectional"))
      (node (ref "U$65") (pin "1") (pinfunction "VCC_1") (pintype "bidirectional"))
      (node (ref "U$66") (pin "1") (pinfunction "VCC_1") (pintype "bidirectional"))
      (node (ref "U$67") (pin "1") (pinfunction "VCC_1") (pintype "bidirectional"))
      (node (ref "U$68") (pin "1") (pinfunction "VCC_1") (pintype "bidirectional"))
      (node (ref "U$69") (pin "1") (pinfunction "VCC_1") (pintype "bidirectional"))
      (node (ref "U$7") (pin "1") (pinfunction "VCC_1") (pintype "bidirectional"))
      (node (ref "U$70") (pin "1") (pinfunction "VCC_1") (pintype "bidirectional"))
      (node (ref "U$71") (pin "1") (pinfunction "VCC_1") (pintype "bidirectional"))
      (node (ref "U$72") (pin "1") (pinfunction "VCC_1") (pintype "bidirectional"))
      (node (ref "U$73") (pin "1") (pinfunction "VCC_1") (pintype "bidirectional"))
      (node (ref "U$74") (pin "1") (pinfunction "VCC_1") (pintype "bidirectional"))
      (node (ref "U$75") (pin "1") (pinfunction "VCC_1") (pintype "bidirectional"))
      (node (ref "U$76") (pin "1") (pinfunction "VCC_1") (pintype "bidirectional"))
      (node (ref "U$77") (pin "1") (pinfunction "VCC_1") (pintype "bidirectional"))
      (node (ref "U$78") (pin "1") (pinfunction "VCC_1") (pintype "bidirectional"))
      (node (ref "U$8") (pin "1") (pinfunction "VCC_1") (pintype "bidirectional"))
      (node (ref "U$9") (pin "1") (pinfunction "VCC_1") (pintype "bidirectional"))
    )
    (net (code "2") (name "GND") (class "Default")
      (node (ref "C1") (pin "2") (pinfunction "2_2") (pintype "passive"))
      (node (ref "C10") (pin "2") (pinfunction "2_2") (pintype "passive"))
      (node (ref "C11") (pin "2") (pinfunction "2_2") (pintype "passive"))
      (node (ref "C12") (pin "2") (pinfunction "2_2") (pintype "passive"))
      (node (ref "C13") (pin "2") (pinfunction "2_2") (pintype "passive"))
      (node (ref "C14") (pin "2") (pinfunction "2_2") (pintype "passive"))
      (node (ref "C15") (pin "2") (pinfunction "2_2") (pintype "passive"))
      (node (ref "C16") (pin "2") (pinfunction "2_2") (pintype "passive"))
      (node (ref "C17") (pin "2") (pinfunction "2_2") (pintype "passive"))
      (node (ref "C18") (pin "2") (pinfunction "2_2") (pintype "passive"))
      (node (ref "C19") (pin "2") (pinfunction "2_2") (pintype "passive"))
      (node (ref "C2") (pin "2") (pinfunction "2_2") (pintype "passive"))
      (node (ref "C20") (pin "2") (pinfunction "2_2") (pintype "passive"))
      (node (ref "C21") (pin "2") (pinfunction "2_2") (pintype "passive"))
      (node (ref "C22") (pin "2") (pinfunction "2_2") (pintype "passive"))
      (node (ref "C23") (pin "2") (pinfunction "2_2") (pintype "passive"))
      (node (ref "C24") (pin "2") (pinfunction "2_2") (pintype "passive"))
      (node (ref "C25") (pin "2") (pinfunction "2_2") (pintype "passive"))
      (node (ref "C26") (pin "2") (pinfunction "2_2") (pintype "passive"))
      (node (ref "C27") (pin "2") (pinfunction "2_2") (pintype "passive"))
      (node (ref "C28") (pin "2") (pinfunction "2_2") (pintype "passive"))
      (node (ref "C29") (pin "2") (pinfunction "2_2") (pintype "passive"))
      (node (ref "C3") (pin "2") (pinfunction "2_2") (pintype "passive"))
      (node (ref "C30") (pin "2") (pinfunction "2_2") (pintype "passive"))
      (node (ref "C31") (pin "2") (pinfunction "2_2") (pintype "passive"))
      (node (ref "C32") (pin "2") (pinfunction "2_2") (pintype "passive"))
      (node (ref "C33") (pin "2") (pinfunction "2_2") (pintype "passive"))
      (node (ref "C34") (pin "2") (pinfunction "2_2") (pintype "passive"))
      (node (ref "C35") (pin "2") (pinfunction "2_2") (pintype "passive"))
      (node (ref "C36") (pin "2") (pinfunction "2_2") (pintype "passive"))
      (node (ref "C37") (pin "2") (pinfunction "2_2") (pintype "passive"))
      (node (ref "C38") (pin "2") (pinfunction "2_2") (pintype "passive"))
      (node (ref "C39") (pin "2") (pinfunction "2_2") (pintype "passive"))
      (node (ref "C4") (pin "2") (pinfunction "2_2") (pintype "passive"))
      (node (ref "C40") (pin "2") (pinfunction "2_2") (pintype "passive"))
      (node (ref "C41") (pin "2") (pinfunction "2_2") (pintype "passive"))
      (node (ref "C42") (pin "2") (pinfunction "2_2") (pintype "passive"))
      (node (ref "C43") (pin "2") (pinfunction "2_2") (pintype "passive"))
      (node (ref "C44") (pin "2") (pinfunction "2_2") (pintype "passive"))
      (node (ref "C45") (pin "2") (pinfunction "2_2") (pintype "passive"))
      (node (ref "C46") (pin "2") (pinfunction "2_2") (pintype "passive"))
      (node (ref "C47") (pin "2") (pinfunction "2_2") (pintype "passive"))
      (node (ref "C48") (pin "2") (pinfunction "2_2") (pintype "passive"))
      (node (ref "C49") (pin "2") (pinfunction "2_2") (pintype "passive"))
      (node (ref "C5") (pin "2") (pinfunction "2_2") (pintype "passive"))
      (node (ref "C50") (pin "2") (pinfunction "2_2") (pintype "passive"))
      (node (ref "C51") (pin "2") (pinfunction "2_2") (pintype "passive"))
      (node (ref "C52") (pin "2") (pinfunction "2_2") (pintype "passive"))
      (node (ref "C53") (pin "2") (pinfunction "2_2") (pintype "passive"))
      (node (ref "C54") (pin "2") (pinfunction "2_2") (pintype "passive"))
      (node (ref "C55") (pin "2") (pinfunction "2_2") (pintype "passive"))
      (node (ref "C56") (pin "2") (pinfunction "2_2") (pintype "passive"))
      (node (ref "C57") (pin "2") (pinfunction "2_2") (pintype "passive"))
      (node (ref "C58") (pin "2") (pinfunction "2_2") (pintype "passive"))
      (node (ref "C59") (pin "2") (pinfunction "2_2") (pintype "passive"))
      (node (ref "C6") (pin "2") (pinfunction "2_2") (pintype "passive"))
      (node (ref "C60") (pin "2") (pinfunction "2_2") (pintype "passive"))
      (node (ref "C61") (pin "2") (pinfunction "2_2") (pintype "passive"))
      (node (ref "C62") (pin "2") (pinfunction "2_2") (pintype "passive"))
      (node (ref "C63") (pin "2") (pinfunction "2_2") (pintype "passive"))
      (node (ref "C64") (pin "2") (pinfunction "2_2") (pintype "passive"))
      (node (ref "C65") (pin "2") (pinfunction "2_2") (pintype "passive"))
      (node (ref "C66") (pin "2") (pinfunction "2_2") (pintype "passive"))
      (node (ref "C67") (pin "2") (pinfunction "2_2") (pintype "passive"))
      (node (ref "C68") (pin "2") (pinfunction "2_2") (pintype "passive"))
      (node (ref "C69") (pin "2") (pinfunction "2_2") (pintype "passive"))
      (node (ref "C7") (pin "2") (pinfunction "2_2") (pintype "passive"))
      (node (ref "C70") (pin "2") (pinfunction "2_2") (pintype "passive"))
      (node (ref "C71") (pin "2") (pinfunction "2_2") (pintype "passive"))
      (node (ref "C72") (pin "2") (pinfunction "2_2") (pintype "passive"))
      (node (ref "C73") (pin "2") (pinfunction "2_2") (pintype "passive"))
      (node (ref "C74") (pin "2") (pinfunction "2_2") (pintype "passive"))
      (node (ref "C75") (pin "2") (pinfunction "2_2") (pintype "passive"))
      (node (ref "C76") (pin "2") (pinfunction "2_2") (pintype "passive"))
      (node (ref "C77") (pin "2") (pinfunction "2_2") (pintype "passive"))
      (node (ref "C78") (pin "2") (pinfunction "2_2") (pintype "passive"))
      (node (ref "C79") (pin "C") (pinfunction "-_C") (pintype "passive"))
      (node (ref "C8") (pin "2") (pinfunction "2_2") (pintype "passive"))
      (node (ref "C84") (pin "C") (pinfunction "-_C") (pintype "passive"))
      (node (ref "C9") (pin "2") (pinfunction "2_2") (pintype "passive"))
      (node (ref "GND") (pin "1") (pinfunction "P_1") (pintype "passive"))
      (node (ref "U$1") (pin "6") (pinfunction "GND_6") (pintype "bidirectional"))
      (node (ref "U$10") (pin "6") (pinfunction "GND_6") (pintype "bidirectional"))
      (node (ref "U$11") (pin "6") (pinfunction "GND_6") (pintype "bidirectional"))
      (node (ref "U$12") (pin "6") (pinfunction "GND_6") (pintype "bidirectional"))
      (node (ref "U$13") (pin "6") (pinfunction "GND_6") (pintype "bidirectional"))
      (node (ref "U$14") (pin "6") (pinfunction "GND_6") (pintype "bidirectional"))
      (node (ref "U$15") (pin "6") (pinfunction "GND_6") (pintype "bidirectional"))
      (node (ref "U$16") (pin "6") (pinfunction "GND_6") (pintype "bidirectional"))
      (node (ref "U$17") (pin "6") (pinfunction "GND_6") (pintype "bidirectional"))
      (node (ref "U$18") (pin "6") (pinfunction "GND_6") (pintype "bidirectional"))
      (node (ref "U$19") (pin "6") (pinfunction "GND_6") (pintype "bidirectional"))
      (node (ref "U$2") (pin "6") (pinfunction "GND_6") (pintype "bidirectional"))
      (node (ref "U$20") (pin "6") (pinfunction "GND_6") (pintype "bidirectional"))
      (node (ref "U$21") (pin "6") (pinfunction "GND_6") (pintype "bidirectional"))
      (node (ref "U$22") (pin "6") (pinfunction "GND_6") (pintype "bidirectional"))
      (node (ref "U$23") (pin "6") (pinfunction "GND_6") (pintype "bidirectional"))
      (node (ref "U$24") (pin "6") (pinfunction "GND_6") (pintype "bidirectional"))
      (node (ref "U$25") (pin "6") (pinfunction "GND_6") (pintype "bidirectional"))
      (node (ref "U$26") (pin "6") (pinfunction "GND_6") (pintype "bidirectional"))
      (node (ref "U$27") (pin "6") (pinfunction "GND_6") (pintype "bidirectional"))
      (node (ref "U$28") (pin "6") (pinfunction "GND_6") (pintype "bidirectional"))
      (node (ref "U$29") (pin "6") (pinfunction "GND_6") (pintype "bidirectional"))
      (node (ref "U$3") (pin "6") (pinfunction "GND_6") (pintype "bidirectional"))
      (node (ref "U$30") (pin "6") (pinfunction "GND_6") (pintype "bidirectional"))
      (node (ref "U$31") (pin "6") (pinfunction "GND_6") (pintype "bidirectional"))
      (node (ref "U$32") (pin "6") (pinfunction "GND_6") (pintype "bidirectional"))
      (node (ref "U$33") (pin "6") (pinfunction "GND_6") (pintype "bidirectional"))
      (node (ref "U$34") (pin "6") (pinfunction "GND_6") (pintype "bidirectional"))
      (node (ref "U$35") (pin "6") (pinfunction "GND_6") (pintype "bidirectional"))
      (node (ref "U$36") (pin "6") (pinfunction "GND_6") (pintype "bidirectional"))
      (node (ref "U$37") (pin "6") (pinfunction "GND_6") (pintype "bidirectional"))
      (node (ref "U$38") (pin "6") (pinfunction "GND_6") (pintype "bidirectional"))
      (node (ref "U$39") (pin "6") (pinfunction "GND_6") (pintype "bidirectional"))
      (node (ref "U$4") (pin "6") (pinfunction "GND_6") (pintype "bidirectional"))
      (node (ref "U$40") (pin "6") (pinfunction "GND_6") (pintype "bidirectional"))
      (node (ref "U$41") (pin "6") (pinfunction "GND_6") (pintype "bidirectional"))
      (node (ref "U$42") (pin "6") (pinfunction "GND_6") (pintype "bidirectional"))
      (node (ref "U$43") (pin "6") (pinfunction "GND_6") (pintype "bidirectional"))
      (node (ref "U$44") (pin "6") (pinfunction "GND_6") (pintype "bidirectional"))
      (node (ref "U$45") (pin "6") (pinfunction "GND_6") (pintype "bidirectional"))
      (node (ref "U$46") (pin "6") (pinfunction "GND_6") (pintype "bidirectional"))
      (node (ref "U$47") (pin "6") (pinfunction "GND_6") (pintype "bidirectional"))
      (node (ref "U$48") (pin "6") (pinfunction "GND_6") (pintype "bidirectional"))
      (node (ref "U$49") (pin "6") (pinfunction "GND_6") (pintype "bidirectional"))
      (node (ref "U$5") (pin "6") (pinfunction "GND_6") (pintype "bidirectional"))
      (node (ref "U$50") (pin "6") (pinfunction "GND_6") (pintype "bidirectional"))
      (node (ref "U$51") (pin "6") (pinfunction "GND_6") (pintype "bidirectional"))
      (node (ref "U$52") (pin "6") (pinfunction "GND_6") (pintype "bidirectional"))
      (node (ref "U$53") (pin "6") (pinfunction "GND_6") (pintype "bidirectional"))
      (node (ref "U$54") (pin "6") (pinfunction "GND_6") (pintype "bidirectional"))
      (node (ref "U$55") (pin "6") (pinfunction "GND_6") (pintype "bidirectional"))
      (node (ref "U$56") (pin "6") (pinfunction "GND_6") (pintype "bidirectional"))
      (node (ref "U$57") (pin "6") (pinfunction "GND_6") (pintype "bidirectional"))
      (node (ref "U$58") (pin "6") (pinfunction "GND_6") (pintype "bidirectional"))
      (node (ref "U$59") (pin "6") (pinfunction "GND_6") (pintype "bidirectional"))
      (node (ref "U$6") (pin "6") (pinfunction "GND_6") (pintype "bidirectional"))
      (node (ref "U$60") (pin "6") (pinfunction "GND_6") (pintype "bidirectional"))
      (node (ref "U$61") (pin "6") (pinfunction "GND_6") (pintype "bidirectional"))
      (node (ref "U$62") (pin "6") (pinfunction "GND_6") (pintype "bidirectional"))
      (node (ref "U$63") (pin "6") (pinfunction "GND_6") (pintype "bidirectional"))
      (node (ref "U$64") (pin "6") (pinfunction "GND_6") (pintype "bidirectional"))
      (node (ref "U$65") (pin "6") (pinfunction "GND_6") (pintype "bidirectional"))
      (node (ref "U$66") (pin "6") (pinfunction "GND_6") (pintype "bidirectional"))
      (node (ref "U$67") (pin "6") (pinfunction "GND_6") (pintype "bidirectional"))
      (node (ref "U$68") (pin "6") (pinfunction "GND_6") (pintype "bidirectional"))
      (node (ref "U$69") (pin "6") (pinfunction "GND_6") (pintype "bidirectional"))
      (node (ref "U$7") (pin "6") (pinfunction "GND_6") (pintype "bidirectional"))
      (node (ref "U$70") (pin "6") (pinfunction "GND_6") (pintype "bidirectional"))
      (node (ref "U$71") (pin "6") (pinfunction "GND_6") (pintype "bidirectional"))
      (node (ref "U$72") (pin "6") (pinfunction "GND_6") (pintype "bidirectional"))
      (node (ref "U$73") (pin "6") (pinfunction "GND_6") (pintype "bidirectional"))
      (node (ref "U$74") (pin "6") (pinfunction "GND_6") (pintype "bidirectional"))
      (node (ref "U$75") (pin "6") (pinfunction "GND_6") (pintype "bidirectional"))
      (node (ref "U$76") (pin "6") (pinfunction "GND_6") (pintype "bidirectional"))
      (node (ref "U$77") (pin "6") (pinfunction "GND_6") (pintype "bidirectional"))
      (node (ref "U$78") (pin "6") (pinfunction "GND_6") (pintype "bidirectional"))
      (node (ref "U$8") (pin "6") (pinfunction "GND_6") (pintype "bidirectional"))
      (node (ref "U$9") (pin "6") (pinfunction "GND_6") (pintype "bidirectional"))
    )
    (net (code "3") (name "Net-(+12V-P)") (class "Default")
      (node (ref "+12V") (pin "1") (pinfunction "P_1") (pintype "passive"))
      (node (ref "C84") (pin "A") (pinfunction "+_A") (pintype "passive"))
      (node (ref "IC1") (pin "3") (pinfunction "IN_3") (pintype "input"))
    )
    (net (code "4") (name "Net-(CI-P)") (class "Default")
      (node (ref "CI") (pin "1") (pinfunction "P_1") (pintype "passive"))
      (node (ref "U$1") (pin "5") (pinfunction "CI_5") (pintype "bidirectional"))
    )
    (net (code "5") (name "Net-(CO-P)") (class "Default")
      (node (ref "CO") (pin "1") (pinfunction "P_1") (pintype "passive"))
      (node (ref "U$78") (pin "2") (pinfunction "CO_2") (pintype "bidirectional"))
    )
    (net (code "6") (name "Net-(DI-P)") (class "Default")
      (node (ref "DI") (pin "1") (pinfunction "P_1") (pintype "passive"))
      (node (ref "U$1") (pin "4") (pinfunction "DI_4") (pintype "bidirectional"))
    )
    (net (code "7") (name "Net-(DO-P)") (class "Default")
      (node (ref "DO") (pin "1") (pinfunction "P_1") (pintype "passive"))
      (node (ref "U$78") (pin "3") (pinfunction "DO_3") (pintype "bidirectional"))
    )
    (net (code "8") (name "Net-(U$1-CO)") (class "Default")
      (node (ref "U$1") (pin "2") (pinfunction "CO_2") (pintype "bidirectional"))
      (node (ref "U$2") (pin "5") (pinfunction "CI_5") (pintype "bidirectional"))
    )
    (net (code "9") (name "Net-(U$1-DO)") (class "Default")
      (node (ref "U$1") (pin "3") (pinfunction "DO_3") (pintype "bidirectional"))
      (node (ref "U$2") (pin "4") (pinfunction "DI_4") (pintype "bidirectional"))
    )
    (net (code "10") (name "Net-(U$2-CO)") (class "Default")
      (node (ref "U$2") (pin "2") (pinfunction "CO_2") (pintype "bidirectional"))
      (node (ref "U$3") (pin "5") (pinfunction "CI_5") (pintype "bidirectional"))
    )
    (net (code "11") (name "Net-(U$2-DO)") (class "Default")
      (node (ref "U$2") (pin "3") (pinfunction "DO_3") (pintype "bidirectional"))
      (node (ref "U$3") (pin "4") (pinfunction "DI_4") (pintype "bidirectional"))
    )
    (net (code "12") (name "Net-(U$3-CO)") (class "Default")
      (node (ref "U$3") (pin "2") (pinfunction "CO_2") (pintype "bidirectional"))
      (node (ref "U$4") (pin "5") (pinfunction "CI_5") (pintype "bidirectional"))
    )
    (net (code "13") (name "Net-(U$3-DO)") (class "Default")
      (node (ref "U$3") (pin "3") (pinfunction "DO_3") (pintype "bidirectional"))
      (node (ref "U$4") (pin "4") (pinfunction "DI_4") (pintype "bidirectional"))
    )
    (net (code "14") (name "Net-(U$4-CO)") (class "Default")
      (node (ref "U$4") (pin "2") (pinfunction "CO_2") (pintype "bidirectional"))
      (node (ref "U$5") (pin "5") (pinfunction "CI_5") (pintype "bidirectional"))
    )
    (net (code "15") (name "Net-(U$4-DO)") (class "Default")
      (node (ref "U$4") (pin "3") (pinfunction "DO_3") (pintype "bidirectional"))
      (node (ref "U$5") (pin "4") (pinfunction "DI_4") (pintype "bidirectional"))
    )
    (net (code "16") (name "Net-(U$5-CO)") (class "Default")
      (node (ref "U$5") (pin "2") (pinfunction "CO_2") (pintype "bidirectional"))
      (node (ref "U$6") (pin "5") (pinfunction "CI_5") (pintype "bidirectional"))
    )
    (net (code "17") (name "Net-(U$5-DO)") (class "Default")
      (node (ref "U$5") (pin "3") (pinfunction "DO_3") (pintype "bidirectional"))
      (node (ref "U$6") (pin "4") (pinfunction "DI_4") (pintype "bidirectional"))
    )
    (net (code "18") (name "Net-(U$6-CO)") (class "Default")
      (node (ref "U$6") (pin "2") (pinfunction "CO_2") (pintype "bidirectional"))
      (node (ref "U$7") (pin "5") (pinfunction "CI_5") (pintype "bidirectional"))
    )
    (net (code "19") (name "Net-(U$6-DO)") (class "Default")
      (node (ref "U$6") (pin "3") (pinfunction "DO_3") (pintype "bidirectional"))
      (node (ref "U$7") (pin "4") (pinfunction "DI_4") (pintype "bidirectional"))
    )
    (net (code "20") (name "Net-(U$7-CO)") (class "Default")
      (node (ref "U$7") (pin "2") (pinfunction "CO_2") (pintype "bidirectional"))
      (node (ref "U$8") (pin "5") (pinfunction "CI_5") (pintype "bidirectional"))
    )
    (net (code "21") (name "Net-(U$7-DO)") (class "Default")
      (node (ref "U$7") (pin "3") (pinfunction "DO_3") (pintype "bidirectional"))
      (node (ref "U$8") (pin "4") (pinfunction "DI_4") (pintype "bidirectional"))
    )
    (net (code "22") (name "Net-(U$8-CO)") (class "Default")
      (node (ref "U$8") (pin "2") (pinfunction "CO_2") (pintype "bidirectional"))
      (node (ref "U$9") (pin "5") (pinfunction "CI_5") (pintype "bidirectional"))
    )
    (net (code "23") (name "Net-(U$8-DO)") (class "Default")
      (node (ref "U$8") (pin "3") (pinfunction "DO_3") (pintype "bidirectional"))
      (node (ref "U$9") (pin "4") (pinfunction "DI_4") (pintype "bidirectional"))
    )
    (net (code "24") (name "Net-(U$10-CI)") (class "Default")
      (node (ref "U$10") (pin "5") (pinfunction "CI_5") (pintype "bidirectional"))
      (node (ref "U$9") (pin "2") (pinfunction "CO_2") (pintype "bidirectional"))
    )
    (net (code "25") (name "Net-(U$10-CO)") (class "Default")
      (node (ref "U$10") (pin "2") (pinfunction "CO_2") (pintype "bidirectional"))
      (node (ref "U$11") (pin "5") (pinfunction "CI_5") (pintype "bidirectional"))
    )
    (net (code "26") (name "Net-(U$10-DI)") (class "Default")
      (node (ref "U$10") (pin "4") (pinfunction "DI_4") (pintype "bidirectional"))
      (node (ref "U$9") (pin "3") (pinfunction "DO_3") (pintype "bidirectional"))
    )
    (net (code "27") (name "Net-(U$10-DO)") (class "Default")
      (node (ref "U$10") (pin "3") (pinfunction "DO_3") (pintype "bidirectional"))
      (node (ref "U$11") (pin "4") (pinfunction "DI_4") (pintype "bidirectional"))
    )
    (net (code "28") (name "Net-(U$11-CO)") (class "Default")
      (node (ref "U$11") (pin "2") (pinfunction "CO_2") (pintype "bidirectional"))
      (node (ref "U$12") (pin "5") (pinfunction "CI_5") (pintype "bidirectional"))
    )
    (net (code "29") (name "Net-(U$11-DO)") (class "Default")
      (node (ref "U$11") (pin "3") (pinfunction "DO_3") (pintype "bidirectional"))
      (node (ref "U$12") (pin "4") (pinfunction "DI_4") (pintype "bidirectional"))
    )
    (net (code "30") (name "Net-(U$12-CO)") (class "Default")
      (node (ref "U$12") (pin "2") (pinfunction "CO_2") (pintype "bidirectional"))
      (node (ref "U$13") (pin "5") (pinfunction "CI_5") (pintype "bidirectional"))
    )
    (net (code "31") (name "Net-(U$12-DO)") (class "Default")
      (node (ref "U$12") (pin "3") (pinfunction "DO_3") (pintype "bidirectional"))
      (node (ref "U$13") (pin "4") (pinfunction "DI_4") (pintype "bidirectional"))
    )
    (net (code "32") (name "Net-(U$13-CO)") (class "Default")
      (node (ref "U$13") (pin "2") (pinfunction "CO_2") (pintype "bidirectional"))
      (node (ref "U$14") (pin "5") (pinfunction "CI_5") (pintype "bidirectional"))
    )
    (net (code "33") (name "Net-(U$13-DO)") (class "Default")
      (node (ref "U$13") (pin "3") (pinfunction "DO_3") (pintype "bidirectional"))
      (node (ref "U$14") (pin "4") (pinfunction "DI_4") (pintype "bidirectional"))
    )
    (net (code "34") (name "Net-(U$14-CO)") (class "Default")
      (node (ref "U$14") (pin "2") (pinfunction "CO_2") (pintype "bidirectional"))
      (node (ref "U$15") (pin "5") (pinfunction "CI_5") (pintype "bidirectional"))
    )
    (net (code "35") (name "Net-(U$14-DO)") (class "Default")
      (node (ref "U$14") (pin "3") (pinfunction "DO_3") (pintype "bidirectional"))
      (node (ref "U$15") (pin "4") (pinfunction "DI_4") (pintype "bidirectional"))
    )
    (net (code "36") (name "Net-(U$15-CO)") (class "Default")
      (node (ref "U$15") (pin "2") (pinfunction "CO_2") (pintype "bidirectional"))
      (node (ref "U$16") (pin "5") (pinfunction "CI_5") (pintype "bidirectional"))
    )
    (net (code "37") (name "Net-(U$15-DO)") (class "Default")
      (node (ref "U$15") (pin "3") (pinfunction "DO_3") (pintype "bidirectional"))
      (node (ref "U$16") (pin "4") (pinfunction "DI_4") (pintype "bidirectional"))
    )
    (net (code "38") (name "Net-(U$16-CO)") (class "Default")
      (node (ref "U$16") (pin "2") (pinfunction "CO_2") (pintype "bidirectional"))
      (node (ref "U$17") (pin "5") (pinfunction "CI_5") (pintype "bidirectional"))
    )
    (net (code "39") (name "Net-(U$16-DO)") (class "Default")
      (node (ref "U$16") (pin "3") (pinfunction "DO_3") (pintype "bidirectional"))
      (node (ref "U$17") (pin "4") (pinfunction "DI_4") (pintype "bidirectional"))
    )
    (net (code "40") (name "Net-(U$17-CO)") (class "Default")
      (node (ref "U$17") (pin "2") (pinfunction "CO_2") (pintype "bidirectional"))
      (node (ref "U$18") (pin "5") (pinfunction "CI_5") (pintype "bidirectional"))
    )
    (net (code "41") (name "Net-(U$17-DO)") (class "Default")
      (node (ref "U$17") (pin "3") (pinfunction "DO_3") (pintype "bidirectional"))
      (node (ref "U$18") (pin "4") (pinfunction "DI_4") (pintype "bidirectional"))
    )
    (net (code "42") (name "Net-(U$18-CO)") (class "Default")
      (node (ref "U$18") (pin "2") (pinfunction "CO_2") (pintype "bidirectional"))
      (node (ref "U$19") (pin "5") (pinfunction "CI_5") (pintype "bidirectional"))
    )
    (net (code "43") (name "Net-(U$18-DO)") (class "Default")
      (node (ref "U$18") (pin "3") (pinfunction "DO_3") (pintype "bidirectional"))
      (node (ref "U$19") (pin "4") (pinfunction "DI_4") (pintype "bidirectional"))
    )
    (net (code "44") (name "Net-(U$19-CO)") (class "Default")
      (node (ref "U$19") (pin "2") (pinfunction "CO_2") (pintype "bidirectional"))
      (node (ref "U$20") (pin "5") (pinfunction "CI_5") (pintype "bidirectional"))
    )
    (net (code "45") (name "Net-(U$19-DO)") (class "Default")
      (node (ref "U$19") (pin "3") (pinfunction "DO_3") (pintype "bidirectional"))
      (node (ref "U$20") (pin "4") (pinfunction "DI_4") (pintype "bidirectional"))
    )
    (net (code "46") (name "Net-(U$20-CO)") (class "Default")
      (node (ref "U$20") (pin "2") (pinfunction "CO_2") (pintype "bidirectional"))
      (node (ref "U$21") (pin "5") (pinfunction "CI_5") (pintype "bidirectional"))
    )
    (net (code "47") (name "Net-(U$20-DO)") (class "Default")
      (node (ref "U$20") (pin "3") (pinfunction "DO_3") (pintype "bidirectional"))
      (node (ref "U$21") (pin "4") (pinfunction "DI_4") (pintype "bidirectional"))
    )
    (net (code "48") (name "Net-(U$21-CO)") (class "Default")
      (node (ref "U$21") (pin "2") (pinfunction "CO_2") (pintype "bidirectional"))
      (node (ref "U$22") (pin "5") (pinfunction "CI_5") (pintype "bidirectional"))
    )
    (net (code "49") (name "Net-(U$21-DO)") (class "Default")
      (node (ref "U$21") (pin "3") (pinfunction "DO_3") (pintype "bidirectional"))
      (node (ref "U$22") (pin "4") (pinfunction "DI_4") (pintype "bidirectional"))
    )
    (net (code "50") (name "Net-(U$22-CO)") (class "Default")
      (node (ref "U$22") (pin "2") (pinfunction "CO_2") (pintype "bidirectional"))
      (node (ref "U$23") (pin "5") (pinfunction "CI_5") (pintype "bidirectional"))
    )
    (net (code "51") (name "Net-(U$22-DO)") (class "Default")
      (node (ref "U$22") (pin "3") (pinfunction "DO_3") (pintype "bidirectional"))
      (node (ref "U$23") (pin "4") (pinfunction "DI_4") (pintype "bidirectional"))
    )
    (net (code "52") (name "Net-(U$23-CO)") (class "Default")
      (node (ref "U$23") (pin "2") (pinfunction "CO_2") (pintype "bidirectional"))
      (node (ref "U$24") (pin "5") (pinfunction "CI_5") (pintype "bidirectional"))
    )
    (net (code "53") (name "Net-(U$23-DO)") (class "Default")
      (node (ref "U$23") (pin "3") (pinfunction "DO_3") (pintype "bidirectional"))
      (node (ref "U$24") (pin "4") (pinfunction "DI_4") (pintype "bidirectional"))
    )
    (net (code "54") (name "Net-(U$24-CO)") (class "Default")
      (node (ref "U$24") (pin "2") (pinfunction "CO_2") (pintype "bidirectional"))
      (node (ref "U$25") (pin "5") (pinfunction "CI_5") (pintype "bidirectional"))
    )
    (net (code "55") (name "Net-(U$24-DO)") (class "Default")
      (node (ref "U$24") (pin "3") (pinfunction "DO_3") (pintype "bidirectional"))
      (node (ref "U$25") (pin "4") (pinfunction "DI_4") (pintype "bidirectional"))
    )
    (net (code "56") (name "Net-(U$25-CO)") (class "Default")
      (node (ref "U$25") (pin "2") (pinfunction "CO_2") (pintype "bidirectional"))
      (node (ref "U$26") (pin "5") (pinfunction "CI_5") (pintype "bidirectional"))
    )
    (net (code "57") (name "Net-(U$25-DO)") (class "Default")
      (node (ref "U$25") (pin "3") (pinfunction "DO_3") (pintype "bidirectional"))
      (node (ref "U$26") (pin "4") (pinfunction "DI_4") (pintype "bidirectional"))
    )
    (net (code "58") (name "Net-(U$26-CO)") (class "Default")
      (node (ref "U$26") (pin "2") (pinfunction "CO_2") (pintype "bidirectional"))
      (node (ref "U$27") (pin "5") (pinfunction "CI_5") (pintype "bidirectional"))
    )
    (net (code "59") (name "Net-(U$26-DO)") (class "Default")
      (node (ref "U$26") (pin "3") (pinfunction "DO_3") (pintype "bidirectional"))
      (node (ref "U$27") (pin "4") (pinfunction "DI_4") (pintype "bidirectional"))
    )
    (net (code "60") (name "Net-(U$27-CO)") (class "Default")
      (node (ref "U$27") (pin "2") (pinfunction "CO_2") (pintype "bidirectional"))
      (node (ref "U$28") (pin "5") (pinfunction "CI_5") (pintype "bidirectional"))
    )
    (net (code "61") (name "Net-(U$27-DO)") (class "Default")
      (node (ref "U$27") (pin "3") (pinfunction "DO_3") (pintype "bidirectional"))
      (node (ref "U$28") (pin "4") (pinfunction "DI_4") (pintype "bidirectional"))
    )
    (net (code "62") (name "Net-(U$28-CO)") (class "Default")
      (node (ref "U$28") (pin "2") (pinfunction "CO_2") (pintype "bidirectional"))
      (node (ref "U$29") (pin "5") (pinfunction "CI_5") (pintype "bidirectional"))
    )
    (net (code "63") (name "Net-(U$28-DO)") (class "Default")
      (node (ref "U$28") (pin "3") (pinfunction "DO_3") (pintype "bidirectional"))
      (node (ref "U$29") (pin "4") (pinfunction "DI_4") (pintype "bidirectional"))
    )
    (net (code "64") (name "Net-(U$29-CO)") (class "Default")
      (node (ref "U$29") (pin "2") (pinfunction "CO_2") (pintype "bidirectional"))
      (node (ref "U$30") (pin "5") (pinfunction "CI_5") (pintype "bidirectional"))
    )
    (net (code "65") (name "Net-(U$29-DO)") (class "Default")
      (node (ref "U$29") (pin "3") (pinfunction "DO_3") (pintype "bidirectional"))
      (node (ref "U$30") (pin "4") (pinfunction "DI_4") (pintype "bidirectional"))
    )
    (net (code "66") (name "Net-(U$30-CO)") (class "Default")
      (node (ref "U$30") (pin "2") (pinfunction "CO_2") (pintype "bidirectional"))
      (node (ref "U$31") (pin "5") (pinfunction "CI_5") (pintype "bidirectional"))
    )
    (net (code "67") (name "Net-(U$30-DO)") (class "Default")
      (node (ref "U$30") (pin "3") (pinfunction "DO_3") (pintype "bidirectional"))
      (node (ref "U$31") (pin "4") (pinfunction "DI_4") (pintype "bidirectional"))
    )
    (net (code "68") (name "Net-(U$31-CO)") (class "Default")
      (node (ref "U$31") (pin "2") (pinfunction "CO_2") (pintype "bidirectional"))
      (node (ref "U$32") (pin "5") (pinfunction "CI_5") (pintype "bidirectional"))
    )
    (net (code "69") (name "Net-(U$31-DO)") (class "Default")
      (node (ref "U$31") (pin "3") (pinfunction "DO_3") (pintype "bidirectional"))
      (node (ref "U$32") (pin "4") (pinfunction "DI_4") (pintype "bidirectional"))
    )
    (net (code "70") (name "Net-(U$32-CO)") (class "Default")
      (node (ref "U$32") (pin "2") (pinfunction "CO_2") (pintype "bidirectional"))
      (node (ref "U$33") (pin "5") (pinfunction "CI_5") (pintype "bidirectional"))
    )
    (net (code "71") (name "Net-(U$32-DO)") (class "Default")
      (node (ref "U$32") (pin "3") (pinfunction "DO_3") (pintype "bidirectional"))
      (node (ref "U$33") (pin "4") (pinfunction "DI_4") (pintype "bidirectional"))
    )
    (net (code "72") (name "Net-(U$33-CO)") (class "Default")
      (node (ref "U$33") (pin "2") (pinfunction "CO_2") (pintype "bidirectional"))
      (node (ref "U$34") (pin "5") (pinfunction "CI_5") (pintype "bidirectional"))
    )
    (net (code "73") (name "Net-(U$33-DO)") (class "Default")
      (node (ref "U$33") (pin "3") (pinfunction "DO_3") (pintype "bidirectional"))
      (node (ref "U$34") (pin "4") (pinfunction "DI_4") (pintype "bidirectional"))
    )
    (net (code "74") (name "Net-(U$34-CO)") (class "Default")
      (node (ref "U$34") (pin "2") (pinfunction "CO_2") (pintype "bidirectional"))
      (node (ref "U$35") (pin "5") (pinfunction "CI_5") (pintype "bidirectional"))
    )
    (net (code "75") (name "Net-(U$34-DO)") (class "Default")
      (node (ref "U$34") (pin "3") (pinfunction "DO_3") (pintype "bidirectional"))
      (node (ref "U$35") (pin "4") (pinfunction "DI_4") (pintype "bidirectional"))
    )
    (net (code "76") (name "Net-(U$35-CO)") (class "Default")
      (node (ref "U$35") (pin "2") (pinfunction "CO_2") (pintype "bidirectional"))
      (node (ref "U$36") (pin "5") (pinfunction "CI_5") (pintype "bidirectional"))
    )
    (net (code "77") (name "Net-(U$35-DO)") (class "Default")
      (node (ref "U$35") (pin "3") (pinfunction "DO_3") (pintype "bidirectional"))
      (node (ref "U$36") (pin "4") (pinfunction "DI_4") (pintype "bidirectional"))
    )
    (net (code "78") (name "Net-(U$36-CO)") (class "Default")
      (node (ref "U$36") (pin "2") (pinfunction "CO_2") (pintype "bidirectional"))
      (node (ref "U$37") (pin "5") (pinfunction "CI_5") (pintype "bidirectional"))
    )
    (net (code "79") (name "Net-(U$36-DO)") (class "Default")
      (node (ref "U$36") (pin "3") (pinfunction "DO_3") (pintype "bidirectional"))
      (node (ref "U$37") (pin "4") (pinfunction "DI_4") (pintype "bidirectional"))
    )
    (net (code "80") (name "Net-(U$37-CO)") (class "Default")
      (node (ref "U$37") (pin "2") (pinfunction "CO_2") (pintype "bidirectional"))
      (node (ref "U$38") (pin "5") (pinfunction "CI_5") (pintype "bidirectional"))
    )
    (net (code "81") (name "Net-(U$37-DO)") (class "Default")
      (node (ref "U$37") (pin "3") (pinfunction "DO_3") (pintype "bidirectional"))
      (node (ref "U$38") (pin "4") (pinfunction "DI_4") (pintype "bidirectional"))
    )
    (net (code "82") (name "Net-(U$38-CO)") (class "Default")
      (node (ref "U$38") (pin "2") (pinfunction "CO_2") (pintype "bidirectional"))
      (node (ref "U$39") (pin "5") (pinfunction "CI_5") (pintype "bidirectional"))
    )
    (net (code "83") (name "Net-(U$38-DO)") (class "Default")
      (node (ref "U$38") (pin "3") (pinfunction "DO_3") (pintype "bidirectional"))
      (node (ref "U$39") (pin "4") (pinfunction "DI_4") (pintype "bidirectional"))
    )
    (net (code "84") (name "Net-(U$39-CO)") (class "Default")
      (node (ref "U$39") (pin "2") (pinfunction "CO_2") (pintype "bidirectional"))
      (node (ref "U$40") (pin "5") (pinfunction "CI_5") (pintype "bidirectional"))
    )
    (net (code "85") (name "Net-(U$39-DO)") (class "Default")
      (node (ref "U$39") (pin "3") (pinfunction "DO_3") (pintype "bidirectional"))
      (node (ref "U$40") (pin "4") (pinfunction "DI_4") (pintype "bidirectional"))
    )
    (net (code "86") (name "Net-(U$40-CO)") (class "Default")
      (node (ref "U$40") (pin "2") (pinfunction "CO_2") (pintype "bidirectional"))
      (node (ref "U$41") (pin "5") (pinfunction "CI_5") (pintype "bidirectional"))
    )
    (net (code "87") (name "Net-(U$40-DO)") (class "Default")
      (node (ref "U$40") (pin "3") (pinfunction "DO_3") (pintype "bidirectional"))
      (node (ref "U$41") (pin "4") (pinfunction "DI_4") (pintype "bidirectional"))
    )
    (net (code "88") (name "Net-(U$41-CO)") (class "Default")
      (node (ref "U$41") (pin "2") (pinfunction "CO_2") (pintype "bidirectional"))
      (node (ref "U$42") (pin "5") (pinfunction "CI_5") (pintype "bidirectional"))
    )
    (net (code "89") (name "Net-(U$41-DO)") (class "Default")
      (node (ref "U$41") (pin "3") (pinfunction "DO_3") (pintype "bidirectional"))
      (node (ref "U$42") (pin "4") (pinfunction "DI_4") (pintype "bidirectional"))
    )
    (net (code "90") (name "Net-(U$42-CO)") (class "Default")
      (node (ref "U$42") (pin "2") (pinfunction "CO_2") (pintype "bidirectional"))
      (node (ref "U$43") (pin "5") (pinfunction "CI_5") (pintype "bidirectional"))
    )
    (net (code "91") (name "Net-(U$42-DO)") (class "Default")
      (node (ref "U$42") (pin "3") (pinfunction "DO_3") (pintype "bidirectional"))
      (node (ref "U$43") (pin "4") (pinfunction "DI_4") (pintype "bidirectional"))
    )
    (net (code "92") (name "Net-(U$43-CO)") (class "Default")
      (node (ref "U$43") (pin "2") (pinfunction "CO_2") (pintype "bidirectional"))
      (node (ref "U$44") (pin "5") (pinfunction "CI_5") (pintype "bidirectional"))
    )
    (net (code "93") (name "Net-(U$43-DO)") (class "Default")
      (node (ref "U$43") (pin "3") (pinfunction "DO_3") (pintype "bidirectional"))
      (node (ref "U$44") (pin "4") (pinfunction "DI_4") (pintype "bidirectional"))
    )
    (net (code "94") (name "Net-(U$44-CO)") (class "Default")
      (node (ref "U$44") (pin "2") (pinfunction "CO_2") (pintype "bidirectional"))
      (node (ref "U$45") (pin "5") (pinfunction "CI_5") (pintype "bidirectional"))
    )
    (net (code "95") (name "Net-(U$44-DO)") (class "Default")
      (node (ref "U$44") (pin "3") (pinfunction "DO_3") (pintype "bidirectional"))
      (node (ref "U$45") (pin "4") (pinfunction "DI_4") (pintype "bidirectional"))
    )
    (net (code "96") (name "Net-(U$45-CO)") (class "Default")
      (node (ref "U$45") (pin "2") (pinfunction "CO_2") (pintype "bidirectional"))
      (node (ref "U$46") (pin "5") (pinfunction "CI_5") (pintype "bidirectional"))
    )
    (net (code "97") (name "Net-(U$45-DO)") (class "Default")
      (node (ref "U$45") (pin "3") (pinfunction "DO_3") (pintype "bidirectional"))
      (node (ref "U$46") (pin "4") (pinfunction "DI_4") (pintype "bidirectional"))
    )
    (net (code "98") (name "Net-(U$46-CO)") (class "Default")
      (node (ref "U$46") (pin "2") (pinfunction "CO_2") (pintype "bidirectional"))
      (node (ref "U$47") (pin "5") (pinfunction "CI_5") (pintype "bidirectional"))
    )
    (net (code "99") (name "Net-(U$46-DO)") (class "Default")
      (node (ref "U$46") (pin "3") (pinfunction "DO_3") (pintype "bidirectional"))
      (node (ref "U$47") (pin "4") (pinfunction "DI_4") (pintype "bidirectional"))
    )
    (net (code "100") (name "Net-(U$47-CO)") (class "Default")
      (node (ref "U$47") (pin "2") (pinfunction "CO_2") (pintype "bidirectional"))
      (node (ref "U$48") (pin "5") (pinfunction "CI_5") (pintype "bidirectional"))
    )
    (net (code "101") (name "Net-(U$47-DO)") (class "Default")
      (node (ref "U$47") (pin "3") (pinfunction "DO_3") (pintype "bidirectional"))
      (node (ref "U$48") (pin "4") (pinfunction "DI_4") (pintype "bidirectional"))
    )
    (net (code "102") (name "Net-(U$48-CO)") (class "Default")
      (node (ref "U$48") (pin "2") (pinfunction "CO_2") (pintype "bidirectional"))
      (node (ref "U$49") (pin "5") (pinfunction "CI_5") (pintype "bidirectional"))
    )
    (net (code "103") (name "Net-(U$48-DO)") (class "Default")
      (node (ref "U$48") (pin "3") (pinfunction "DO_3") (pintype "bidirectional"))
      (node (ref "U$49") (pin "4") (pinfunction "DI_4") (pintype "bidirectional"))
    )
    (net (code "104") (name "Net-(U$49-CO)") (class "Default")
      (node (ref "U$49") (pin "2") (pinfunction "CO_2") (pintype "bidirectional"))
      (node (ref "U$50") (pin "5") (pinfunction "CI_5") (pintype "bidirectional"))
    )
    (net (code "105") (name "Net-(U$49-DO)") (class "Default")
      (node (ref "U$49") (pin "3") (pinfunction "DO_3") (pintype "bidirectional"))
      (node (ref "U$50") (pin "4") (pinfunction "DI_4") (pintype "bidirectional"))
    )
    (net (code "106") (name "Net-(U$50-CO)") (class "Default")
      (node (ref "U$50") (pin "2") (pinfunction "CO_2") (pintype "bidirectional"))
      (node (ref "U$51") (pin "5") (pinfunction "CI_5") (pintype "bidirectional"))
    )
    (net (code "107") (name "Net-(U$50-DO)") (class "Default")
      (node (ref "U$50") (pin "3") (pinfunction "DO_3") (pintype "bidirectional"))
      (node (ref "U$51") (pin "4") (pinfunction "DI_4") (pintype "bidirectional"))
    )
    (net (code "108") (name "Net-(U$51-CO)") (class "Default")
      (node (ref "U$51") (pin "2") (pinfunction "CO_2") (pintype "bidirectional"))
      (node (ref "U$52") (pin "5") (pinfunction "CI_5") (pintype "bidirectional"))
    )
    (net (code "109") (name "Net-(U$51-DO)") (class "Default")
      (node (ref "U$51") (pin "3") (pinfunction "DO_3") (pintype "bidirectional"))
      (node (ref "U$52") (pin "4") (pinfunction "DI_4") (pintype "bidirectional"))
    )
    (net (code "110") (name "Net-(U$52-CO)") (class "Default")
      (node (ref "U$52") (pin "2") (pinfunction "CO_2") (pintype "bidirectional"))
      (node (ref "U$53") (pin "5") (pinfunction "CI_5") (pintype "bidirectional"))
    )
    (net (code "111") (name "Net-(U$52-DO)") (class "Default")
      (node (ref "U$52") (pin "3") (pinfunction "DO_3") (pintype "bidirectional"))
      (node (ref "U$53") (pin "4") (pinfunction "DI_4") (pintype "bidirectional"))
    )
    (net (code "112") (name "Net-(U$53-CO)") (class "Default")
      (node (ref "U$53") (pin "2") (pinfunction "CO_2") (pintype "bidirectional"))
      (node (ref "U$54") (pin "5") (pinfunction "CI_5") (pintype "bidirectional"))
    )
    (net (code "113") (name "Net-(U$53-DO)") (class "Default")
      (node (ref "U$53") (pin "3") (pinfunction "DO_3") (pintype "bidirectional"))
      (node (ref "U$54") (pin "4") (pinfunction "DI_4") (pintype "bidirectional"))
    )
    (net (code "114") (name "Net-(U$54-CO)") (class "Default")
      (node (ref "U$54") (pin "2") (pinfunction "CO_2") (pintype "bidirectional"))
      (node (ref "U$55") (pin "5") (pinfunction "CI_5") (pintype "bidirectional"))
    )
    (net (code "115") (name "Net-(U$54-DO)") (class "Default")
      (node (ref "U$54") (pin "3") (pinfunction "DO_3") (pintype "bidirectional"))
      (node (ref "U$55") (pin "4") (pinfunction "DI_4") (pintype "bidirectional"))
    )
    (net (code "116") (name "Net-(U$55-CO)") (class "Default")
      (node (ref "U$55") (pin "2") (pinfunction "CO_2") (pintype "bidirectional"))
      (node (ref "U$56") (pin "5") (pinfunction "CI_5") (pintype "bidirectional"))
    )
    (net (code "117") (name "Net-(U$55-DO)") (class "Default")
      (node (ref "U$55") (pin "3") (pinfunction "DO_3") (pintype "bidirectional"))
      (node (ref "U$56") (pin "4") (pinfunction "DI_4") (pintype "bidirectional"))
    )
    (net (code "118") (name "Net-(U$56-CO)") (class "Default")
      (node (ref "U$56") (pin "2") (pinfunction "CO_2") (pintype "bidirectional"))
      (node (ref "U$57") (pin "5") (pinfunction "CI_5") (pintype "bidirectional"))
    )
    (net (code "119") (name "Net-(U$56-DO)") (class "Default")
      (node (ref "U$56") (pin "3") (pinfunction "DO_3") (pintype "bidirectional"))
      (node (ref "U$57") (pin "4") (pinfunction "DI_4") (pintype "bidirectional"))
    )
    (net (code "120") (name "Net-(U$57-CO)") (class "Default")
      (node (ref "U$57") (pin "2") (pinfunction "CO_2") (pintype "bidirectional"))
      (node (ref "U$58") (pin "5") (pinfunction "CI_5") (pintype "bidirectional"))
    )
    (net (code "121") (name "Net-(U$57-DO)") (class "Default")
      (node (ref "U$57") (pin "3") (pinfunction "DO_3") (pintype "bidirectional"))
      (node (ref "U$58") (pin "4") (pinfunction "DI_4") (pintype "bidirectional"))
    )
    (net (code "122") (name "Net-(U$58-CO)") (class "Default")
      (node (ref "U$58") (pin "2") (pinfunction "CO_2") (pintype "bidirectional"))
      (node (ref "U$59") (pin "5") (pinfunction "CI_5") (pintype "bidirectional"))
    )
    (net (code "123") (name "Net-(U$58-DO)") (class "Default")
      (node (ref "U$58") (pin "3") (pinfunction "DO_3") (pintype "bidirectional"))
      (node (ref "U$59") (pin "4") (pinfunction "DI_4") (pintype "bidirectional"))
    )
    (net (code "124") (name "Net-(U$59-CO)") (class "Default")
      (node (ref "U$59") (pin "2") (pinfunction "CO_2") (pintype "bidirectional"))
      (node (ref "U$60") (pin "5") (pinfunction "CI_5") (pintype "bidirectional"))
    )
    (net (code "125") (name "Net-(U$59-DO)") (class "Default")
      (node (ref "U$59") (pin "3") (pinfunction "DO_3") (pintype "bidirectional"))
      (node (ref "U$60") (pin "4") (pinfunction "DI_4") (pintype "bidirectional"))
    )
    (net (code "126") (name "Net-(U$60-CO)") (class "Default")
      (node (ref "U$60") (pin "2") (pinfunction "CO_2") (pintype "bidirectional"))
      (node (ref "U$61") (pin "5") (pinfunction "CI_5") (pintype "bidirectional"))
    )
    (net (code "127") (name "Net-(U$60-DO)") (class "Default")
      (node (ref "U$60") (pin "3") (pinfunction "DO_3") (pintype "bidirectional"))
      (node (ref "U$61") (pin "4") (pinfunction "DI_4") (pintype "bidirectional"))
    )
    (net (code "128") (name "Net-(U$61-CO)") (class "Default")
      (node (ref "U$61") (pin "2") (pinfunction "CO_2") (pintype "bidirectional"))
      (node (ref "U$62") (pin "5") (pinfunction "CI_5") (pintype "bidirectional"))
    )
    (net (code "129") (name "Net-(U$61-DO)") (class "Default")
      (node (ref "U$61") (pin "3") (pinfunction "DO_3") (pintype "bidirectional"))
      (node (ref "U$62") (pin "4") (pinfunction "DI_4") (pintype "bidirectional"))
    )
    (net (code "130") (name "Net-(U$62-CO)") (class "Default")
      (node (ref "U$62") (pin "2") (pinfunction "CO_2") (pintype "bidirectional"))
      (node (ref "U$63") (pin "5") (pinfunction "CI_5") (pintype "bidirectional"))
    )
    (net (code "131") (name "Net-(U$62-DO)") (class "Default")
      (node (ref "U$62") (pin "3") (pinfunction "DO_3") (pintype "bidirectional"))
      (node (ref "U$63") (pin "4") (pinfunction "DI_4") (pintype "bidirectional"))
    )
    (net (code "132") (name "Net-(U$63-CO)") (class "Default")
      (node (ref "U$63") (pin "2") (pinfunction "CO_2") (pintype "bidirectional"))
      (node (ref "U$64") (pin "5") (pinfunction "CI_5") (pintype "bidirectional"))
    )
    (net (code "133") (name "Net-(U$63-DO)") (class "Default")
      (node (ref "U$63") (pin "3") (pinfunction "DO_3") (pintype "bidirectional"))
      (node (ref "U$64") (pin "4") (pinfunction "DI_4") (pintype "bidirectional"))
    )
    (net (code "134") (name "Net-(U$64-CO)") (class "Default")
      (node (ref "U$64") (pin "2") (pinfunction "CO_2") (pintype "bidirectional"))
      (node (ref "U$65") (pin "5") (pinfunction "CI_5") (pintype "bidirectional"))
    )
    (net (code "135") (name "Net-(U$64-DO)") (class "Default")
      (node (ref "U$64") (pin "3") (pinfunction "DO_3") (pintype "bidirectional"))
      (node (ref "U$65") (pin "4") (pinfunction "DI_4") (pintype "bidirectional"))
    )
    (net (code "136") (name "Net-(U$65-CO)") (class "Default")
      (node (ref "U$65") (pin "2") (pinfunction "CO_2") (pintype "bidirectional"))
      (node (ref "U$66") (pin "5") (pinfunction "CI_5") (pintype "bidirectional"))
    )
    (net (code "137") (name "Net-(U$65-DO)") (class "Default")
      (node (ref "U$65") (pin "3") (pinfunction "DO_3") (pintype "bidirectional"))
      (node (ref "U$66") (pin "4") (pinfunction "DI_4") (pintype "bidirectional"))
    )
    (net (code "138") (name "Net-(U$66-CO)") (class "Default")
      (node (ref "U$66") (pin "2") (pinfunction "CO_2") (pintype "bidirectional"))
      (node (ref "U$67") (pin "5") (pinfunction "CI_5") (pintype "bidirectional"))
    )
    (net (code "139") (name "Net-(U$66-DO)") (class "Default")
      (node (ref "U$66") (pin "3") (pinfunction "DO_3") (pintype "bidirectional"))
      (node (ref "U$67") (pin "4") (pinfunction "DI_4") (pintype "bidirectional"))
    )
    (net (code "140") (name "Net-(U$67-CO)") (class "Default")
      (node (ref "U$67") (pin "2") (pinfunction "CO_2") (pintype "bidirectional"))
      (node (ref "U$68") (pin "5") (pinfunction "CI_5") (pintype "bidirectional"))
    )
    (net (code "141") (name "Net-(U$67-DO)") (class "Default")
      (node (ref "U$67") (pin "3") (pinfunction "DO_3") (pintype "bidirectional"))
      (node (ref "U$68") (pin "4") (pinfunction "DI_4") (pintype "bidirectional"))
    )
    (net (code "142") (name "Net-(U$68-CO)") (class "Default")
      (node (ref "U$68") (pin "2") (pinfunction "CO_2") (pintype "bidirectional"))
      (node (ref "U$69") (pin "5") (pinfunction "CI_5") (pintype "bidirectional"))
    )
    (net (code "143") (name "Net-(U$68-DO)") (class "Default")
      (node (ref "U$68") (pin "3") (pinfunction "DO_3") (pintype "bidirectional"))
      (node (ref "U$69") (pin "4") (pinfunction "DI_4") (pintype "bidirectional"))
    )
    (net (code "144") (name "Net-(U$69-CO)") (class "Default")
      (node (ref "U$69") (pin "2") (pinfunction "CO_2") (pintype "bidirectional"))
      (node (ref "U$70") (pin "5") (pinfunction "CI_5") (pintype "bidirectional"))
    )
    (net (code "145") (name "Net-(U$69-DO)") (class "Default")
      (node (ref "U$69") (pin "3") (pinfunction "DO_3") (pintype "bidirectional"))
      (node (ref "U$70") (pin "4") (pinfunction "DI_4") (pintype "bidirectional"))
    )
    (net (code "146") (name "Net-(U$70-CO)") (class "Default")
      (node (ref "U$70") (pin "2") (pinfunction "CO_2") (pintype "bidirectional"))
      (node (ref "U$71") (pin "5") (pinfunction "CI_5") (pintype "bidirectional"))
    )
    (net (code "147") (name "Net-(U$70-DO)") (class "Default")
      (node (ref "U$70") (pin "3") (pinfunction "DO_3") (pintype "bidirectional"))
      (node (ref "U$71") (pin "4") (pinfunction "DI_4") (pintype "bidirectional"))
    )
    (net (code "148") (name "Net-(U$71-CO)") (class "Default")
      (node (ref "U$71") (pin "2") (pinfunction "CO_2") (pintype "bidirectional"))
      (node (ref "U$72") (pin "5") (pinfunction "CI_5") (pintype "bidirectional"))
    )
    (net (code "149") (name "Net-(U$71-DO)") (class "Default")
      (node (ref "U$71") (pin "3") (pinfunction "DO_3") (pintype "bidirectional"))
      (node (ref "U$72") (pin "4") (pinfunction "DI_4") (pintype "bidirectional"))
    )
    (net (code "150") (name "Net-(U$72-CO)") (class "Default")
      (node (ref "U$72") (pin "2") (pinfunction "CO_2") (pintype "bidirectional"))
      (node (ref "U$73") (pin "5") (pinfunction "CI_5") (pintype "bidirectional"))
    )
    (net (code "151") (name "Net-(U$72-DO)") (class "Default")
      (node (ref "U$72") (pin "3") (pinfunction "DO_3") (pintype "bidirectional"))
      (node (ref "U$73") (pin "4") (pinfunction "DI_4") (pintype "bidirectional"))
    )
    (net (code "152") (name "Net-(U$73-CO)") (class "Default")
      (node (ref "U$73") (pin "2") (pinfunction "CO_2") (pintype "bidirectional"))
      (node (ref "U$74") (pin "5") (pinfunction "CI_5") (pintype "bidirectional"))
    )
    (net (code "153") (name "Net-(U$73-DO)") (class "Default")
      (node (ref "U$73") (pin "3") (pinfunction "DO_3") (pintype "bidirectional"))
      (node (ref "U$74") (pin "4") (pinfunction "DI_4") (pintype "bidirectional"))
    )
    (net (code "154") (name "Net-(U$74-CO)") (class "Default")
      (node (ref "U$74") (pin "2") (pinfunction "CO_2") (pintype "bidirectional"))
      (node (ref "U$75") (pin "5") (pinfunction "CI_5") (pintype "bidirectional"))
    )
    (net (code "155") (name "Net-(U$74-DO)") (class "Default")
      (node (ref "U$74") (pin "3") (pinfunction "DO_3") (pintype "bidirectional"))
      (node (ref "U$75") (pin "4") (pinfunction "DI_4") (pintype "bidirectional"))
    )
    (net (code "156") (name "Net-(U$75-CO)") (class "Default")
      (node (ref "U$75") (pin "2") (pinfunction "CO_2") (pintype "bidirectional"))
      (node (ref "U$76") (pin "5") (pinfunction "CI_5") (pintype "bidirectional"))
    )
    (net (code "157") (name "Net-(U$75-DO)") (class "Default")
      (node (ref "U$75") (pin "3") (pinfunction "DO_3") (pintype "bidirectional"))
      (node (ref "U$76") (pin "4") (pinfunction "DI_4") (pintype "bidirectional"))
    )
    (net (code "158") (name "Net-(U$76-CO)") (class "Default")
      (node (ref "U$76") (pin "2") (pinfunction "CO_2") (pintype "bidirectional"))
      (node (ref "U$77") (pin "5") (pinfunction "CI_5") (pintype "bidirectional"))
    )
    (net (code "159") (name "Net-(U$76-DO)") (class "Default")
      (node (ref "U$76") (pin "3") (pinfunction "DO_3") (pintype "bidirectional"))
      (node (ref "U$77") (pin "4") (pinfunction "DI_4") (pintype "bidirectional"))
    )
    (net (code "160") (name "Net-(U$77-CO)") (class "Default")
      (node (ref "U$77") (pin "2") (pinfunction "CO_2") (pintype "bidirectional"))
      (node (ref "U$78") (pin "5") (pinfunction "CI_5") (pintype "bidirectional"))
    )
    (net (code "161") (name "Net-(U$77-DO)") (class "Default")
      (node (ref "U$77") (pin "3") (pinfunction "DO_3") (pintype "bidirectional"))
      (node (ref "U$78") (pin "4") (pinfunction "DI_4") (pintype "bidirectional"))
    )
    (net (code "162") (name "unconnected-(IC1-ADJ-Pad1)") (class "Default")
      (node (ref "IC1") (pin "1") (pinfunction "ADJ_1") (pintype "passive"))
    )
  )
)
